# 20160428.net
KiCad netlist of a schematic drawn in Altium Designer
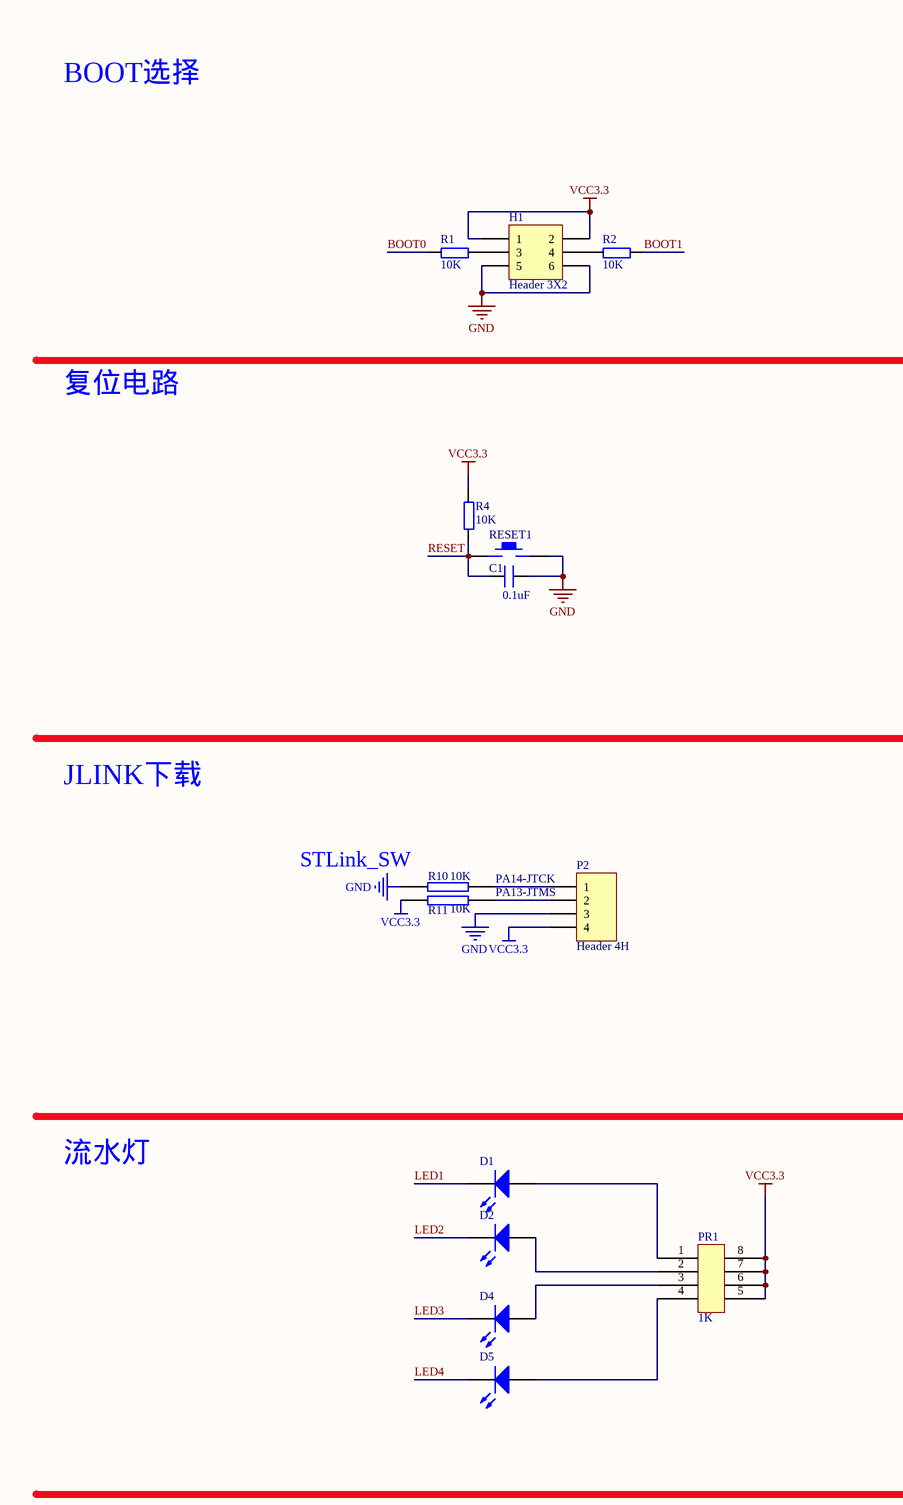
[diagram p0: 主控板20160428.SchDoc, top left]
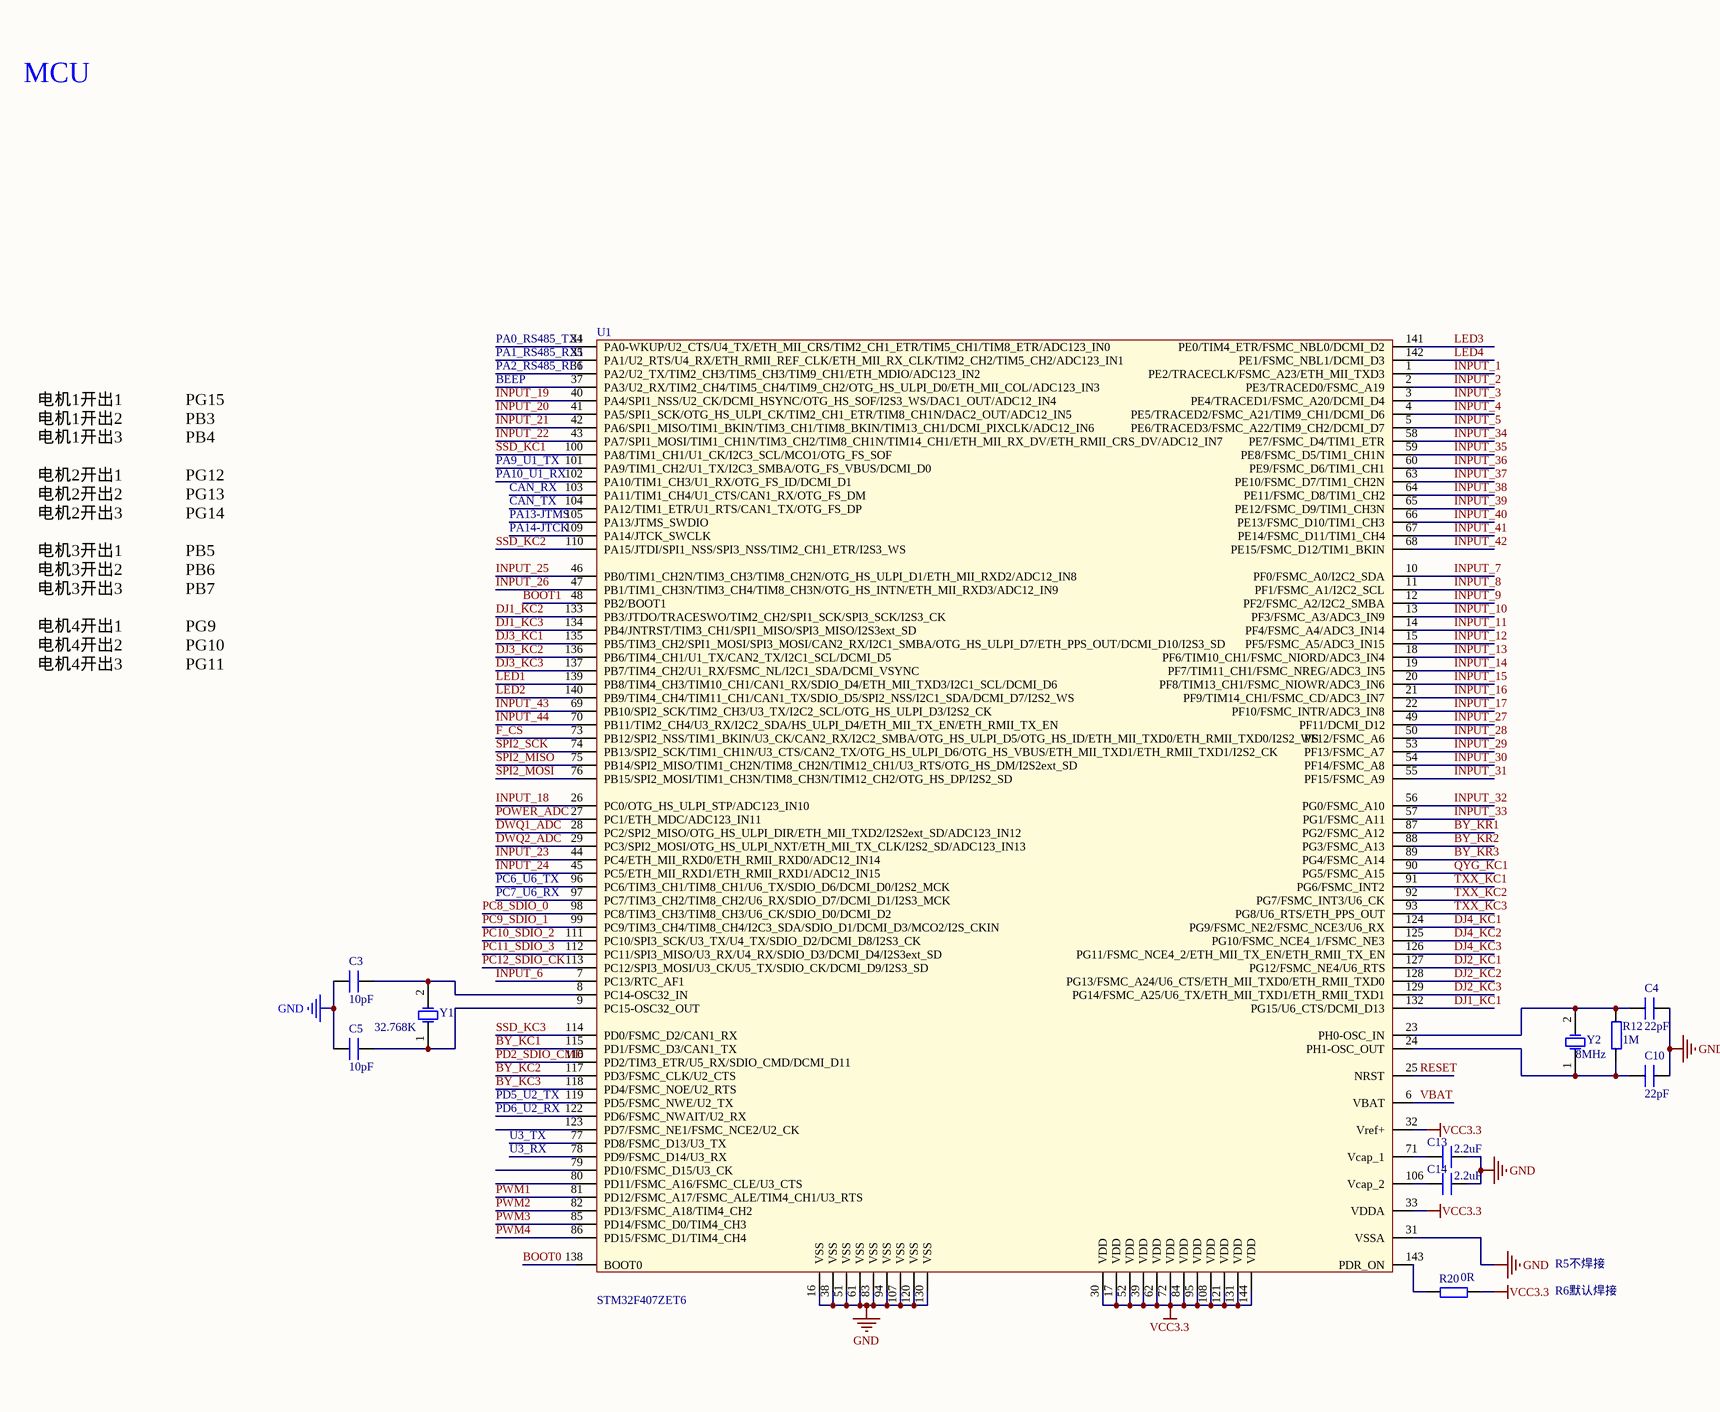
[diagram p1: 主控板20160428.SchDoc, top middle]
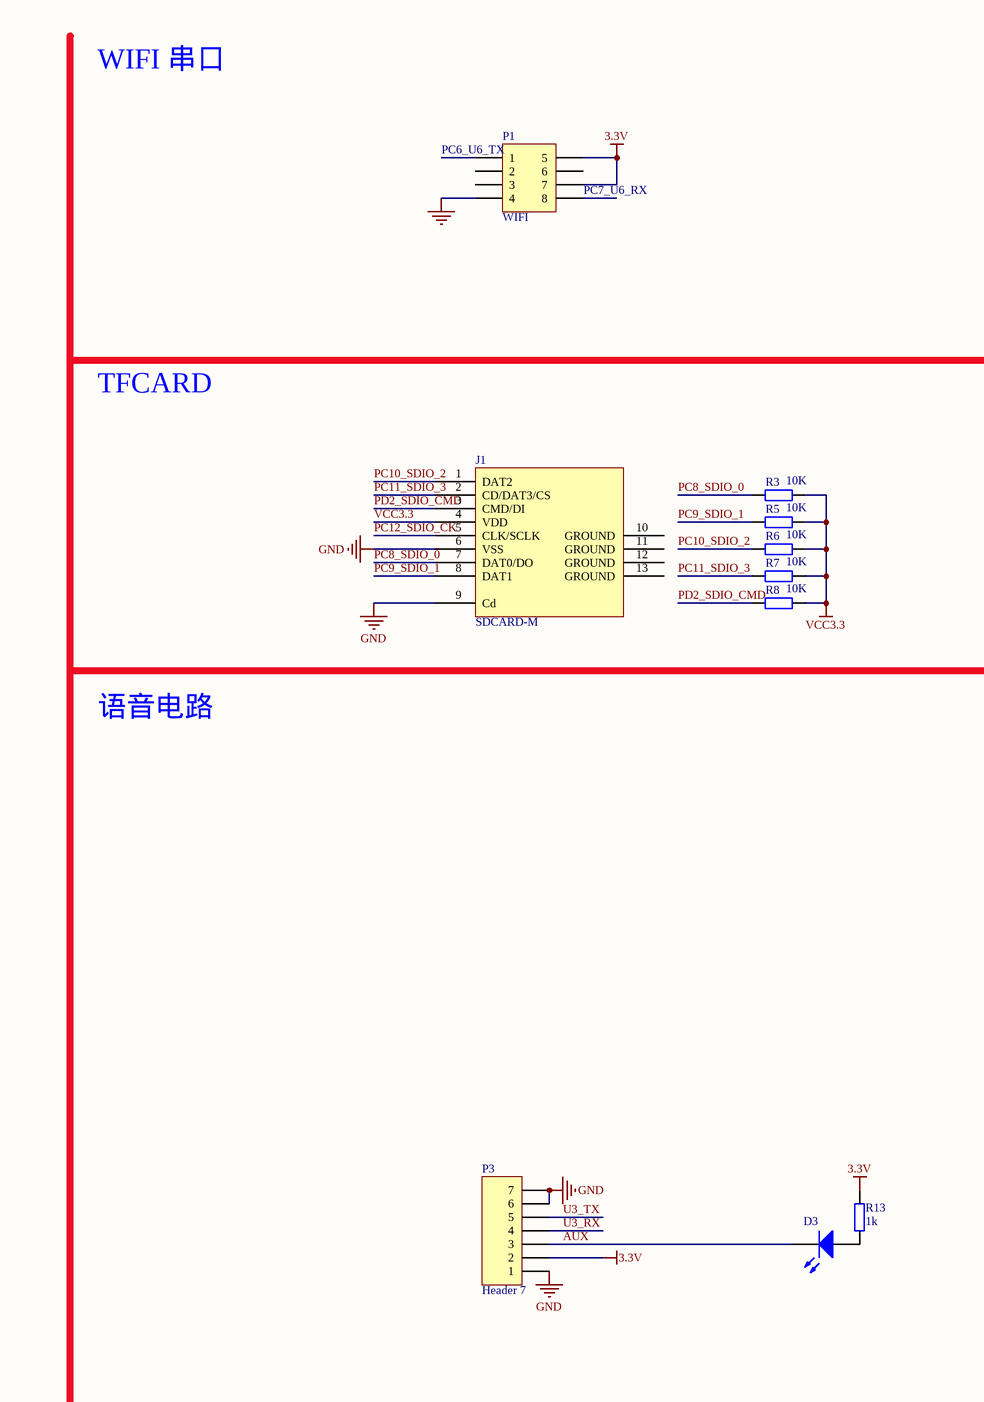
[diagram p2: 主控板20160428.SchDoc, top right]
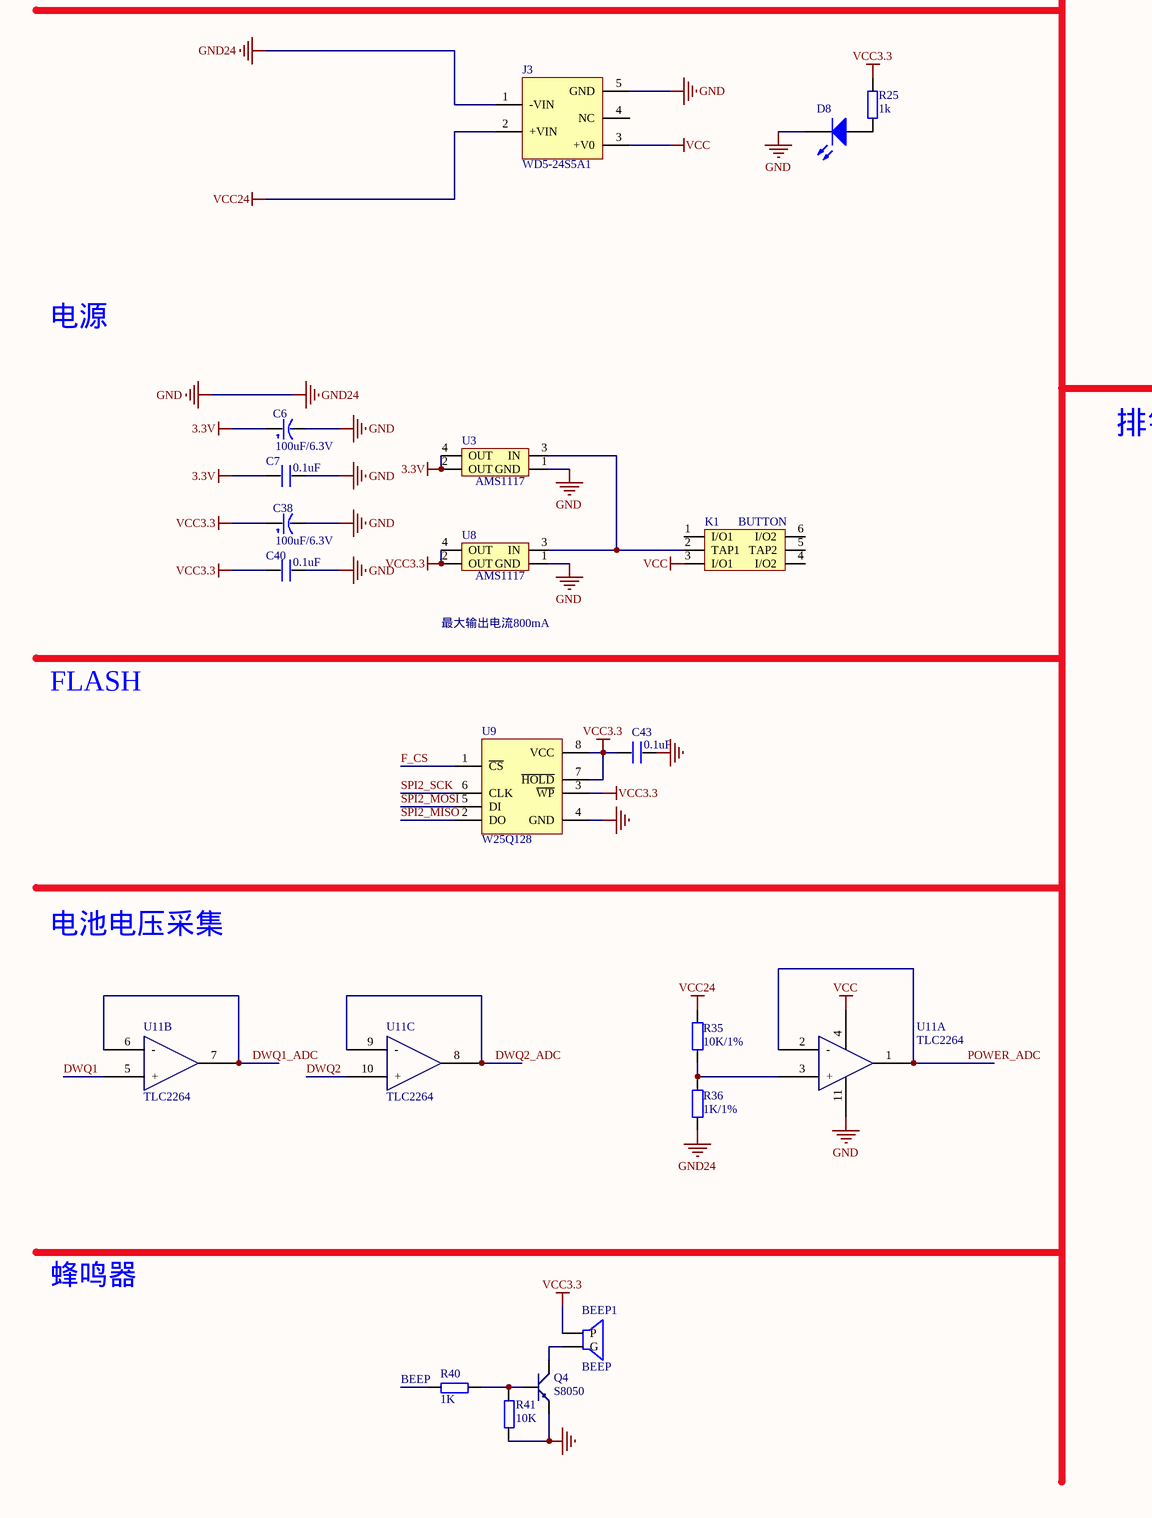
[diagram p3: 主控板20160428.SchDoc, bottom left]
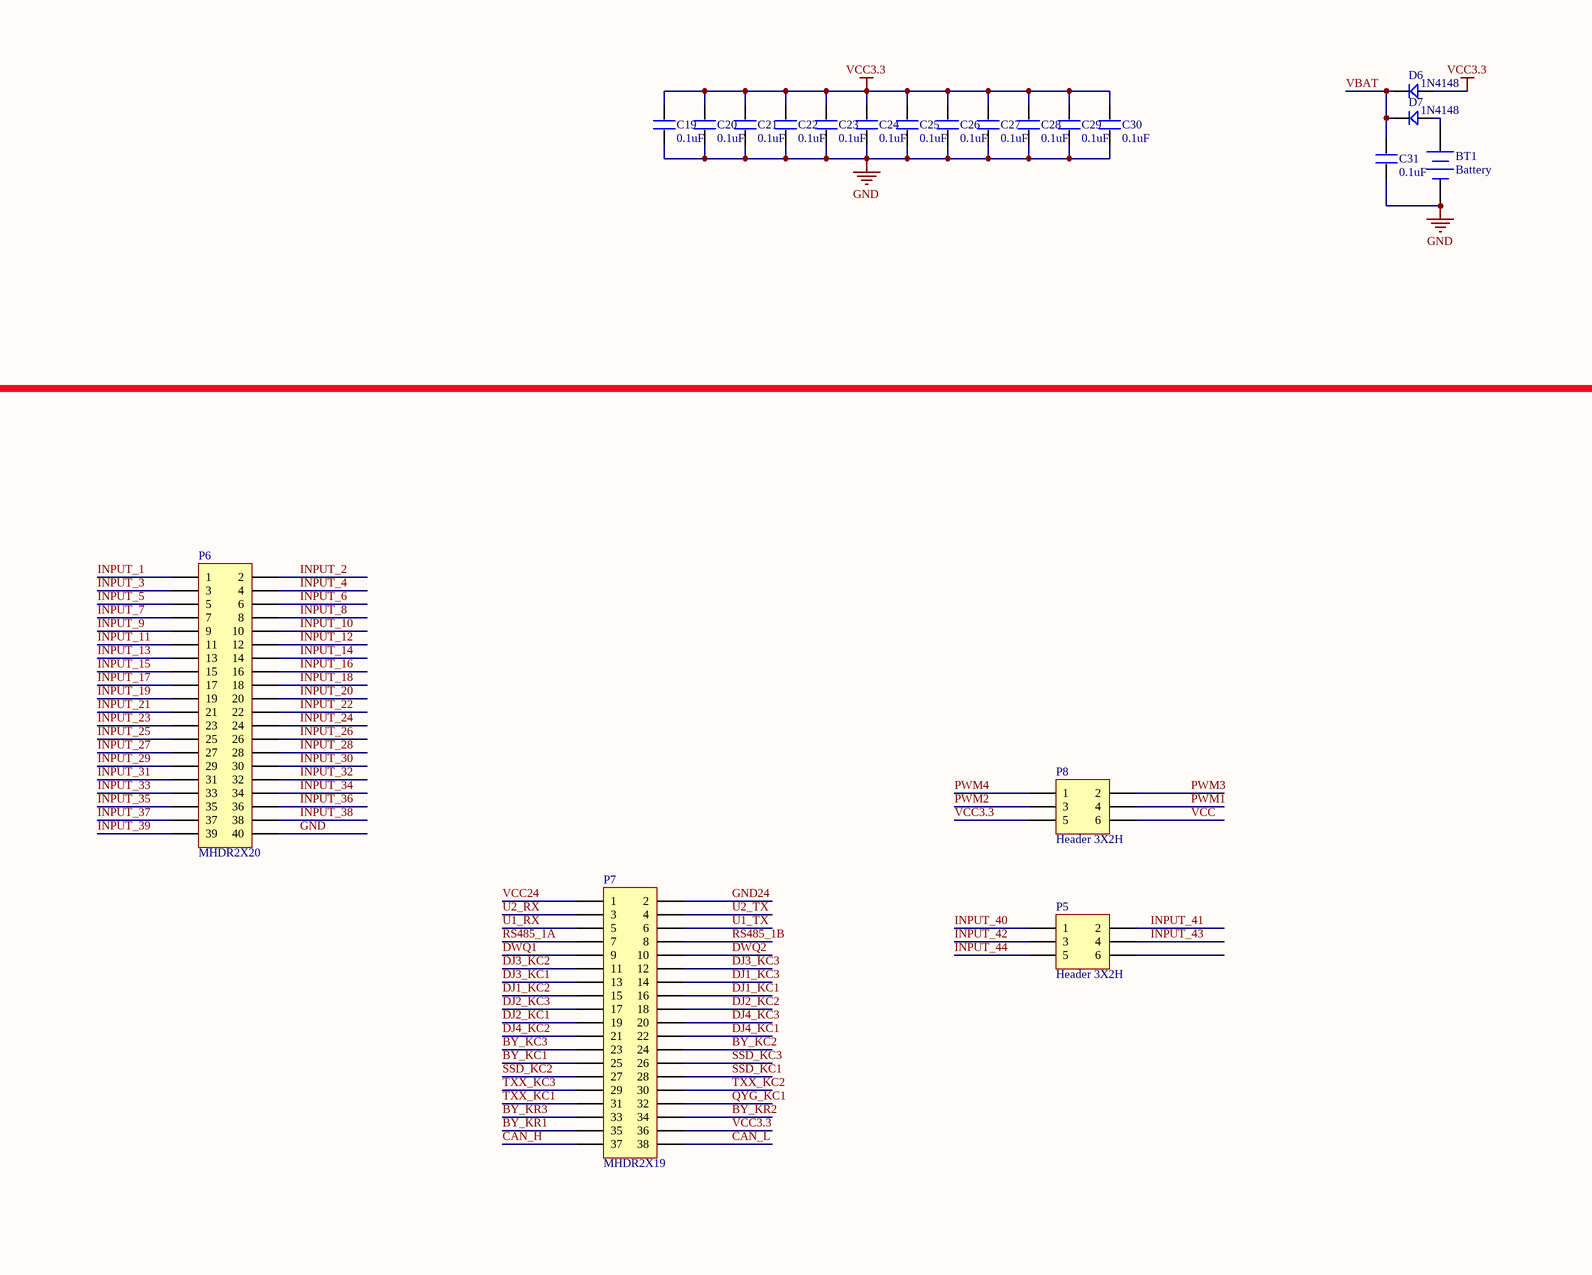
[diagram p4: 主控板20160428.SchDoc, bottom middle]
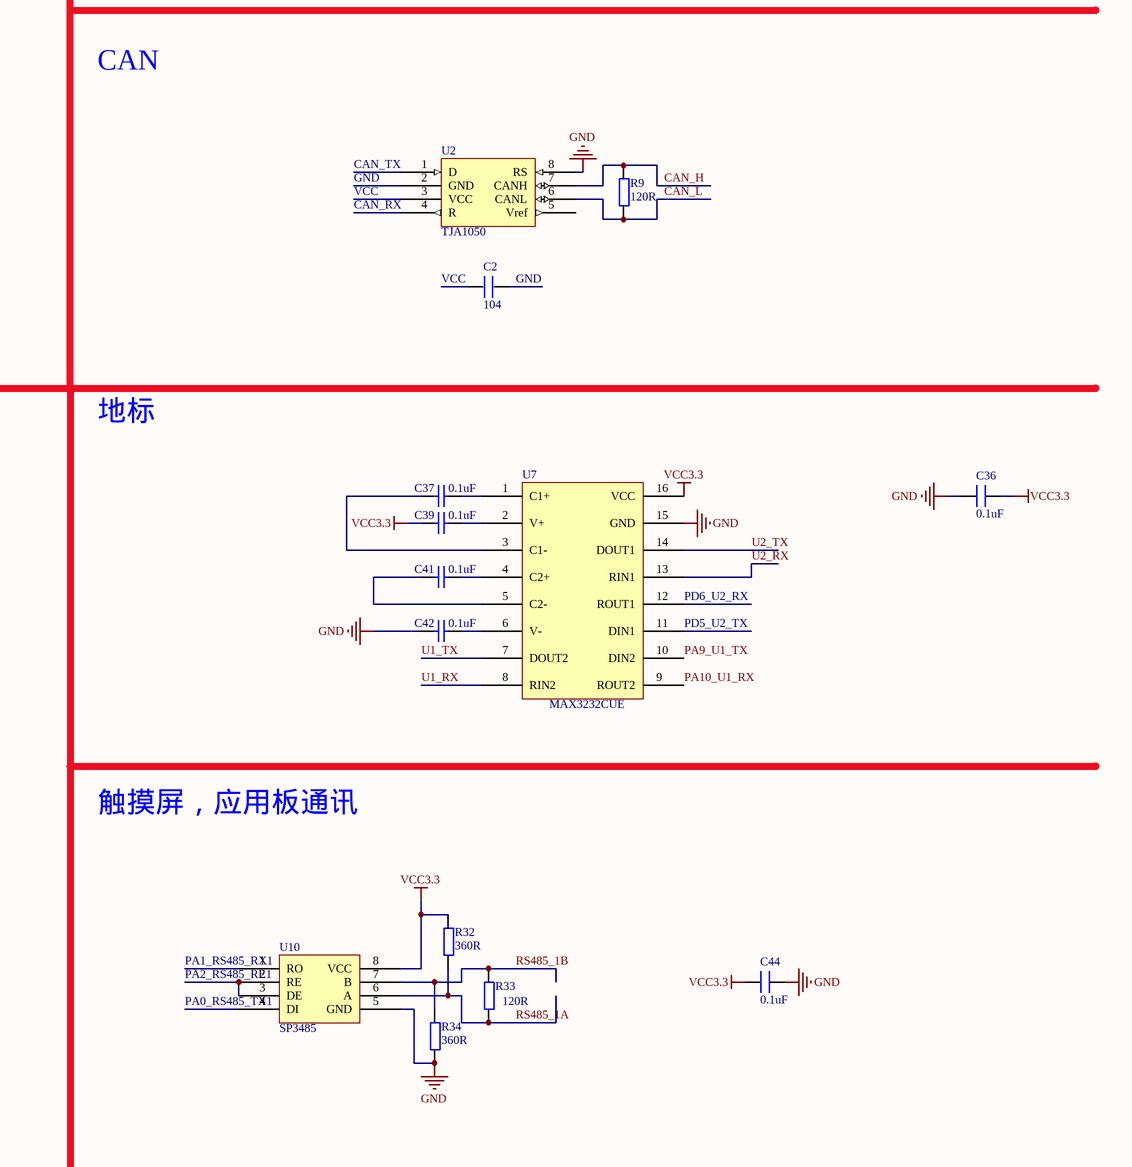
[diagram p5: 主控板20160428.SchDoc, bottom right]

(export (version "E")
  (design (tool "Eeschema 10.0.6"))
  (components
    (comp (ref "BEEP1") (value "BEEP") (footprint "BELL-5") (libsource (lib "WarShip V3_SCH") (part "BEEP")))
    (comp (ref "BT1")
      (value "Battery")
      (footprint "CR1220")
      (description "备份电池")
      (fields (field (name "PUBLISHER") "Altium Limited"))
      (libsource (lib "fszhang") (part "Battery"))
    )
    (comp (ref "C1") (value "0.1uF") (footprint "C0805") (libsource (lib "Explorer STM32F407封装库") (part "C")))
    (comp (ref "C2") (value "104") (footprint "C0805") (libsource (lib "Explorer STM32F407封装库") (part "C_3")))
    (comp (ref "C3")
      (value "10pF")
      (footprint "C0805")
      (libsource (lib "Explorer STM32F407封装库") (part "C_2"))
    )
    (comp (ref "C4")
      (value "22pF")
      (footprint "C0805")
      (libsource (lib "Explorer STM32F407封装库") (part "C_3"))
    )
    (comp (ref "C5")
      (value "10pF")
      (footprint "C0805")
      (libsource (lib "Explorer STM32F407封装库") (part "C_2"))
    )
    (comp (ref "C6") (value "100uF/6.3V") (footprint "3216") (libsource (lib "WarShip V3_SCH") (part "CAP")))
    (comp (ref "C7") (value "0.1uF") (footprint "C0805") (libsource (lib "WarShip V3_SCH") (part "C")))
    (comp (ref "C10")
      (value "22pF")
      (footprint "C0805")
      (libsource (lib "Explorer STM32F407封装库") (part "C_3"))
    )
    (comp (ref "C13")
      (value "2.2uF")
      (footprint "C0805")
      (libsource (lib "Explorer STM32F407封装库") (part "C"))
    )
    (comp (ref "C14")
      (value "2.2uF")
      (footprint "C0805")
      (libsource (lib "Explorer STM32F407封装库") (part "C"))
    )
    (comp (ref "C19") (value "0.1uF") (footprint "C0805") (libsource (lib "WarShip V3_SCH") (part "C")))
    (comp (ref "C20") (value "0.1uF") (footprint "C0805") (libsource (lib "WarShip V3_SCH") (part "C")))
    (comp (ref "C21") (value "0.1uF") (footprint "C0805") (libsource (lib "WarShip V3_SCH") (part "C")))
    (comp (ref "C22") (value "0.1uF") (footprint "C0805") (libsource (lib "WarShip V3_SCH") (part "C")))
    (comp (ref "C23") (value "0.1uF") (footprint "C0805") (libsource (lib "WarShip V3_SCH") (part "C")))
    (comp (ref "C24") (value "0.1uF") (footprint "C0805") (libsource (lib "WarShip V3_SCH") (part "C")))
    (comp (ref "C25") (value "0.1uF") (footprint "C0805") (libsource (lib "WarShip V3_SCH") (part "C")))
    (comp (ref "C26") (value "0.1uF") (footprint "C0805") (libsource (lib "WarShip V3_SCH") (part "C")))
    (comp (ref "C27") (value "0.1uF") (footprint "C0805") (libsource (lib "WarShip V3_SCH") (part "C")))
    (comp (ref "C28") (value "0.1uF") (footprint "C0805") (libsource (lib "WarShip V3_SCH") (part "C")))
    (comp (ref "C29") (value "0.1uF") (footprint "C0805") (libsource (lib "WarShip V3_SCH") (part "C")))
    (comp (ref "C30") (value "0.1uF") (footprint "C0805") (libsource (lib "WarShip V3_SCH") (part "C")))
    (comp (ref "C31")
      (value "0.1uF")
      (footprint "C0805")
      (libsource (lib "Explorer STM32F407封装库") (part "C_3"))
    )
    (comp (ref "C36")
      (value "0.1uF")
      (footprint "C0805")
      (libsource (lib "Explorer STM32F407封装库") (part "C_2"))
    )
    (comp (ref "C37")
      (value "0.1uF")
      (footprint "C0805")
      (description "Capacitor")
      (fields (field (name "PUBLISHER") "Altium Limited"))
      (libsource (lib "Miscellaneous Devices") (part "Cap"))
    )
    (comp (ref "C38") (value "100uF/6.3V") (footprint "3216") (libsource (lib "WarShip V3_SCH") (part "CAP")))
    (comp (ref "C39")
      (value "0.1uF")
      (footprint "C0805")
      (description "Capacitor")
      (fields (field (name "PUBLISHER") "Altium Limited"))
      (libsource (lib "Miscellaneous Devices") (part "Cap"))
    )
    (comp (ref "C40") (value "0.1uF") (footprint "C0805") (libsource (lib "WarShip V3_SCH") (part "C")))
    (comp (ref "C41")
      (value "0.1uF")
      (footprint "C0805")
      (description "Capacitor")
      (fields (field (name "PUBLISHER") "Altium Limited"))
      (libsource (lib "Miscellaneous Devices") (part "Cap"))
    )
    (comp (ref "C42")
      (value "0.1uF")
      (footprint "C0805")
      (description "Capacitor")
      (fields (field (name "PUBLISHER") "Altium Limited"))
      (libsource (lib "Miscellaneous Devices") (part "Cap"))
    )
    (comp (ref "C43") (value "0.1uF") (footprint "C0805") (libsource (lib "WarShip V3_SCH") (part "C")))
    (comp (ref "C44")
      (value "0.1uF")
      (footprint "C0805")
      (libsource (lib "Explorer STM32F407封装库") (part "C_3"))
    )
    (comp (ref "D1")
      (value "LED0")
      (footprint "LC-0805_LED_S1")
      (description "Typical INFRARED GaAs LED")
      (fields (field (name "PUBLISHER") "Altium Limited"))
      (libsource (lib "继电器板_1") (part "LED0"))
    )
    (comp (ref "D2")
      (value "LED0")
      (footprint "LC-0805_LED_S1")
      (description "Typical INFRARED GaAs LED")
      (fields (field (name "PUBLISHER") "Altium Limited"))
      (libsource (lib "继电器板_1") (part "LED0"))
    )
    (comp (ref "D3")
      (value "LED0")
      (footprint "LC-0805_LED_S1")
      (description "Typical INFRARED GaAs LED")
      (fields (field (name "PUBLISHER") "Altium Limited"))
      (libsource (lib "继电器板_1") (part "LED0"))
    )
    (comp (ref "D4")
      (value "LED0")
      (footprint "LC-0805_LED_S1")
      (description "Typical INFRARED GaAs LED")
      (fields (field (name "PUBLISHER") "Altium Limited"))
      (libsource (lib "继电器板_1") (part "LED0"))
    )
    (comp (ref "D5")
      (value "LED0")
      (footprint "LC-0805_LED_S1")
      (description "Typical INFRARED GaAs LED")
      (fields (field (name "PUBLISHER") "Altium Limited"))
      (libsource (lib "继电器板_1") (part "LED0"))
    )
    (comp (ref "D6")
      (value "1N4148")
      (footprint "DIDOE")
      (libsource (lib "Explorer STM32F407封装库") (part "D"))
    )
    (comp (ref "D7")
      (value "1N4148")
      (footprint "DIDOE")
      (libsource (lib "Explorer STM32F407封装库") (part "D"))
    )
    (comp (ref "D8")
      (value "LED0")
      (footprint "LC-0805_LED_S1")
      (description "Typical INFRARED GaAs LED")
      (fields (field (name "PUBLISHER") "Altium Limited"))
      (libsource (lib "继电器板_1") (part "LED0"))
    )
    (comp (ref "H1")
      (value "Header 3X2")
      (footprint "HDR2X3")
      (description "Header, 3-Pin, Dual row")
      (fields (field (name "PUBLISHER") "Altium Limited"))
      (libsource (lib "Explorer STM32F407封装库") (part "Header 3X2"))
    )
    (comp (ref "J1")
      (value "SDCARD-M")
      (footprint "SDCARD-M")
      (description "TF卡槽")
      (libsource (lib "fszhang") (part "SDCARD-M"))
    )
    (comp (ref "J3")
      (value "WD5-24S5A1")
      (footprint "WD5-24S3V3")
      (libsource (lib "*") (part "WD5-24S3V3A1"))
    )
    (comp (ref "K1")
      (value "BUTTON")
      (footprint "BTN8.5*8.5")
      (libsource (lib "WarShip V3_SCH") (part "BUTTON"))
    )
    (comp (ref "P1")
      (value "WIFI")
      (footprint "HDR2X4_CEN")
      (description "Header, 4-Pin, Dual row")
      (fields (field (name "PUBLISHER") "Altium Limited"))
      (libsource (lib "Miscellaneous Connectors") (part "Header 4X2A"))
    )
    (comp (ref "P2")
      (value "Header 4H")
      (footprint "IDE4")
      (description "Header, 4-Pin, Right Angle")
      (fields (field (name "PUBLISHER") "Altium Limited"))
      (libsource (lib "Miscellaneous Connectors") (part "Header 4H"))
    )
    (comp (ref "P3")
      (value "Header 7")
      (footprint "AS50-T27")
      (description "Header, 7-Pin")
      (fields (field (name "PUBLISHER") "Altium Limited"))
      (libsource (lib "Miscellaneous Connectors") (part "Header 7"))
    )
    (comp (ref "P5")
      (value "Header 3X2H")
      (footprint "HDR2X3")
      (description "Header, 3-Pin, Dual row, Right Angle")
      (fields (field (name "PUBLISHER") "Altium Limited"))
      (libsource (lib "Miscellaneous Connectors") (part "Header 3X2H"))
    )
    (comp (ref "P6")
      (value "MHDR2X20")
      (footprint "DIP-2X20")
      (description "Header, 20-Pin, Dual row")
      (fields (field (name "PUBLISHER") "Altium Limited"))
      (libsource (lib "Miscellaneous Connectors") (part "MHDR2X20"))
    )
    (comp (ref "P7")
      (value "MHDR2X19")
      (footprint "DIP-2X19")
      (description "Header, 19-Pin, Dual row")
      (fields (field (name "PUBLISHER") "Altium Limited"))
      (libsource (lib "Miscellaneous Connectors") (part "MHDR2X19"))
    )
    (comp (ref "P8")
      (value "Header 3X2H")
      (footprint "HDR2X3")
      (description "Header, 3-Pin, Dual row, Right Angle")
      (fields (field (name "PUBLISHER") "Altium Limited"))
      (libsource (lib "Miscellaneous Connectors") (part "Header 3X2H"))
    )
    (comp (ref "PR1") (value "1K") (footprint "TPPZ") (libsource (lib "EXPLORER") (part "PZ")))
    (comp (ref "Q4")
      (value "S8050")
      (footprint "SOT-23R")
      (description "8050/BCW846/BCW847")
      (libsource (lib "WarShip V3_SCH") (part "NPN"))
    )
    (comp (ref "R1") (value "10K") (footprint "0805") (libsource (lib "Explorer STM32F407封装库") (part "R_1")))
    (comp (ref "R2") (value "10K") (footprint "0805") (libsource (lib "Explorer STM32F407封装库") (part "R_1")))
    (comp (ref "R3")
      (value "10K")
      (footprint "0805")
      (description "贴片电阻")
      (fields (field (name "PUBLISHER") "Altium Limited"))
      (libsource (lib "fszhang") (part "Res1"))
    )
    (comp (ref "R4") (value "10K") (footprint "0805") (libsource (lib "Explorer STM32F407封装库") (part "R_2")))
    (comp (ref "R5")
      (value "10K")
      (footprint "0805")
      (description "贴片电阻")
      (fields (field (name "PUBLISHER") "Altium Limited"))
      (libsource (lib "fszhang") (part "Res1"))
    )
    (comp (ref "R6")
      (value "10K")
      (footprint "0805")
      (description "贴片电阻")
      (fields (field (name "PUBLISHER") "Altium Limited"))
      (libsource (lib "fszhang") (part "Res1"))
    )
    (comp (ref "R7")
      (value "10K")
      (footprint "0805")
      (description "贴片电阻")
      (fields (field (name "PUBLISHER") "Altium Limited"))
      (libsource (lib "fszhang") (part "Res1"))
    )
    (comp (ref "R8")
      (value "10K")
      (footprint "0805")
      (description "贴片电阻")
      (fields (field (name "PUBLISHER") "Altium Limited"))
      (libsource (lib "fszhang") (part "Res1"))
    )
    (comp (ref "R9") (value "120R") (footprint "0805") (libsource (lib "Explorer STM32F407封装库") (part "R_2")))
    (comp (ref "R10") (value "10K") (footprint "0805") (libsource (lib "*") (part "RES2")))
    (comp (ref "R11") (value "10K") (footprint "0805") (libsource (lib "*") (part "RES2")))
    (comp (ref "R12") (value "1M") (footprint "0805") (libsource (lib "Explorer STM32F407封装库") (part "R")))
    (comp (ref "R13") (value "1k") (footprint "0805") (libsource (lib "Explorer STM32F407封装库") (part "R_2")))
    (comp (ref "R20") (value "0R") (footprint "0805") (libsource (lib "Explorer STM32F407封装库") (part "R_2")))
    (comp (ref "R25") (value "1k") (footprint "0805") (libsource (lib "Explorer STM32F407封装库") (part "R_2")))
    (comp (ref "R32")
      (value "360R")
      (footprint "0805")
      (libsource (lib "Explorer STM32F407封装库") (part "R_2"))
    )
    (comp (ref "R33")
      (value "120R")
      (footprint "0805")
      (libsource (lib "Explorer STM32F407封装库") (part "R_2"))
    )
    (comp (ref "R34")
      (value "360R")
      (footprint "0805")
      (libsource (lib "Explorer STM32F407封装库") (part "R_2"))
    )
    (comp (ref "R35")
      (value "10K/1%")
      (footprint "0805")
      (description "Resistor")
      (fields (field (name "PUBLISHER") "Altium Limited"))
      (libsource (lib "Miscellaneous Devices") (part "Res2"))
    )
    (comp (ref "R36")
      (value "1K/1%")
      (footprint "0805")
      (description "Resistor")
      (fields (field (name "PUBLISHER") "Altium Limited"))
      (libsource (lib "Miscellaneous Devices") (part "Res2"))
    )
    (comp (ref "R40") (value "1K") (footprint "0805") (libsource (lib "WarShip V3_SCH") (part "R")))
    (comp (ref "R41") (value "10K") (footprint "0805") (libsource (lib "WarShip V3_SCH") (part "R")))
    (comp (ref "RESET1")
      (value "KEY_M")
      (footprint "SW_PB2_A1")
      (libsource (lib "Explorer STM32F407封装库") (part "KEY_M"))
    )
    (comp (ref "U1")
      (value "STM32F407ZET6")
      (footprint "LQFP144")
      (libsource (lib "Explorer STM32F407封装库") (part "STM32F407ZET6"))
    )
    (comp (ref "U2")
      (value "TJA1050")
      (footprint "SOP-8")
      (libsource (lib "Explorer STM32F407封装库") (part "SN65HVD230D"))
    )
    (comp (ref "U3")
      (value "AMS1117")
      (footprint "SOT-223")
      (libsource (lib "WarShip V3_SCH") (part "AMS1117"))
    )
    (comp (ref "U7")
      (value "MAX3232CUE")
      (footprint "SO-16")
      (libsource (lib "Smart_board_v1") (part "MAX3232CUE"))
    )
    (comp (ref "U8")
      (value "AMS1117")
      (footprint "SOT-223")
      (libsource (lib "WarShip V3_SCH") (part "AMS1117"))
    )
    (comp (ref "U9")
      (value "W25Q128")
      (footprint "SOIC8_W")
      (description "SPI FLASH")
      (libsource (lib "fszhang") (part "W25QXX"))
    )
    (comp (ref "U10") (value "SP3485") (footprint "SO-8") (libsource (lib "Schlib1") (part "SP3485")))
    (comp (ref "U11") (value "TLC2264") (footprint "SO-14") (libsource (lib "EXPLORER") (part "TLC2264")))
    (comp (ref "Y1")
      (value "32.768K")
      (footprint "XTAL-32768")
      (description "Crystal Oscillator")
      (fields (field (name "PUBLISHER") "Altium Limited"))
      (libsource (lib "Explorer STM32F407封装库") (part "XTAL_1"))
    )
    (comp (ref "Y2")
      (value "8MHz")
      (footprint "XTAL_US")
      (description "Crystal Oscillator")
      (fields (field (name "PUBLISHER") "Altium Limited"))
      (libsource (lib "Explorer STM32F407封装库") (part "XTAL"))
    )
  )
  (nets
    (net (code "1") (name "/AUX") (class "Default")
      (node (ref "D3") (pin "K") (pinfunction "K_K") (pintype "passive"))
      (node (ref "P3") (pin "3") (pinfunction "3_3") (pintype "passive"))
    )
    (net (code "2") (name "/BEEP") (class "Default")
      (node (ref "R40") (pin "1") (pintype "passive"))
      (node (ref "U1") (pin "37") (pinfunction "PA3/U2_RX/TIM2_CH4/TIM5_CH4/TIM9_CH2/OTG_HS_ULPI_D0/ETH_MII_COL/ADC123_IN3_37") (pintype "passive"))
    )
    (net (code "3") (name "/BOOT0") (class "Default")
      (node (ref "R1") (pin "1") (pintype "passive"))
      (node (ref "U1") (pin "138") (pinfunction "BOOT0_138") (pintype "passive"))
    )
    (net (code "4") (name "/BOOT1") (class "Default")
      (node (ref "R2") (pin "2") (pintype "passive"))
      (node (ref "U1") (pin "48") (pinfunction "PB2/BOOT1_48") (pintype "passive"))
    )
    (net (code "5") (name "/BY_KC1") (class "Default")
      (node (ref "P7") (pin "25") (pinfunction "25_25") (pintype "passive"))
      (node (ref "U1") (pin "115") (pinfunction "PD1/FSMC_D3/CAN1_TX_115") (pintype "passive"))
    )
    (net (code "6") (name "/BY_KC2") (class "Default")
      (node (ref "P7") (pin "24") (pinfunction "24_24") (pintype "passive"))
      (node (ref "U1") (pin "117") (pinfunction "PD3/FSMC_CLK/U2_CTS_117") (pintype "passive"))
    )
    (net (code "7") (name "/BY_KC3") (class "Default")
      (node (ref "P7") (pin "23") (pinfunction "23_23") (pintype "passive"))
      (node (ref "U1") (pin "118") (pinfunction "PD4/FSMC_NOE/U2_RTS_118") (pintype "passive"))
    )
    (net (code "8") (name "/BY_KR1") (class "Default")
      (node (ref "P7") (pin "35") (pinfunction "35_35") (pintype "passive"))
      (node (ref "U1") (pin "87") (pinfunction "PG2/FSMC_A12_87") (pintype "passive"))
    )
    (net (code "9") (name "/BY_KR2") (class "Default")
      (node (ref "P7") (pin "34") (pinfunction "34_34") (pintype "passive"))
      (node (ref "U1") (pin "88") (pinfunction "PG3/FSMC_A13_88") (pintype "passive"))
    )
    (net (code "10") (name "/BY_KR3") (class "Default")
      (node (ref "P7") (pin "33") (pinfunction "33_33") (pintype "passive"))
      (node (ref "U1") (pin "89") (pinfunction "PG4/FSMC_A14_89") (pintype "passive"))
    )
    (net (code "11") (name "/CAN_H") (class "Default")
      (node (ref "P7") (pin "37") (pinfunction "37_37") (pintype "passive"))
      (node (ref "R9") (pin "2") (pintype "passive"))
      (node (ref "U2") (pin "7") (pinfunction "CANH_7") (pintype "bidirectional"))
    )
    (net (code "12") (name "/CAN_L") (class "Default")
      (node (ref "P7") (pin "38") (pinfunction "38_38") (pintype "passive"))
      (node (ref "R9") (pin "1") (pintype "passive"))
      (node (ref "U2") (pin "6") (pinfunction "CANL_6") (pintype "bidirectional"))
    )
    (net (code "13") (name "/CAN_RX") (class "Default")
      (node (ref "U1") (pin "103") (pinfunction "PA11/TIM1_CH4/U1_CTS/CAN1_RX/OTG_FS_DM_103") (pintype "passive"))
      (node (ref "U2") (pin "4") (pinfunction "R_4") (pintype "output"))
    )
    (net (code "14") (name "/CAN_TX") (class "Default")
      (node (ref "U1") (pin "104") (pinfunction "PA12/TIM1_ETR/U1_RTS/CAN1_TX/OTG_FS_DP_104") (pintype "passive"))
      (node (ref "U2") (pin "1") (pinfunction "D_1") (pintype "input"))
    )
    (net (code "15") (name "/DJ1_KC1") (class "Default")
      (node (ref "P7") (pin "16") (pinfunction "16_16") (pintype "passive"))
      (node (ref "U1") (pin "132") (pinfunction "PG15/U6_CTS/DCMI_D13_132") (pintype "passive"))
    )
    (net (code "16") (name "/DJ1_KC2") (class "Default")
      (node (ref "P7") (pin "15") (pinfunction "15_15") (pintype "passive"))
      (node (ref "U1") (pin "133") (pinfunction "PB3/JTDO/TRACESWO/TIM2_CH2/SPI1_SCK/SPI3_SCK/I2S3_CK_133") (pintype "passive"))
    )
    (net (code "17") (name "/DJ1_KC3") (class "Default")
      (node (ref "P7") (pin "14") (pinfunction "14_14") (pintype "passive"))
      (node (ref "U1") (pin "134") (pinfunction "PB4/JNTRST/TIM3_CH1/SPI1_MISO/SPI3_MISO/I2S3ext_SD_134") (pintype "passive"))
    )
    (net (code "18") (name "/DJ2_KC1") (class "Default")
      (node (ref "P7") (pin "19") (pinfunction "19_19") (pintype "passive"))
      (node (ref "U1") (pin "127") (pinfunction "PG12/FSMC_NE4/U6_RTS_127") (pintype "passive"))
    )
    (net (code "19") (name "/DJ2_KC2") (class "Default")
      (node (ref "P7") (pin "18") (pinfunction "18_18") (pintype "passive"))
      (node (ref "U1") (pin "128") (pinfunction "PG13/FSMC_A24/U6_CTS/ETH_MII_TXD0/ETH_RMII_TXD0_128") (pintype "passive"))
    )
    (net (code "20") (name "/DJ2_KC3") (class "Default")
      (node (ref "P7") (pin "17") (pinfunction "17_17") (pintype "passive"))
      (node (ref "U1") (pin "129") (pinfunction "PG14/FSMC_A25/U6_TX/ETH_MII_TXD1/ETH_RMII_TXD1_129") (pintype "passive"))
    )
    (net (code "21") (name "/DJ3_KC1") (class "Default")
      (node (ref "P7") (pin "13") (pinfunction "13_13") (pintype "passive"))
      (node (ref "U1") (pin "135") (pinfunction "PB5/TIM3_CH2/SPI1_MOSI/SPI3_MOSI/CAN2_RX/I2C1_SMBA/OTG_HS_ULPI_D7/ETH_PPS_OUT/DCMI_D10/I2S3_SD_135") (pintype "passive"))
    )
    (net (code "22") (name "/DJ3_KC2") (class "Default")
      (node (ref "P7") (pin "11") (pinfunction "11_11") (pintype "passive"))
      (node (ref "U1") (pin "136") (pinfunction "PB6/TIM4_CH1/U1_TX/CAN2_TX/I2C1_SCL/DCMI_D5_136") (pintype "passive"))
    )
    (net (code "23") (name "/DJ3_KC3") (class "Default")
      (node (ref "P7") (pin "12") (pinfunction "12_12") (pintype "passive"))
      (node (ref "U1") (pin "137") (pinfunction "PB7/TIM4_CH2/U1_RX/FSMC_NL/I2C1_SDA/DCMI_VSYNC_137") (pintype "passive"))
    )
    (net (code "24") (name "/DJ4_KC1") (class "Default")
      (node (ref "P7") (pin "22") (pinfunction "22_22") (pintype "passive"))
      (node (ref "U1") (pin "124") (pinfunction "PG9/FSMC_NE2/FSMC_NCE3/U6_RX_124") (pintype "passive"))
    )
    (net (code "25") (name "/DJ4_KC2") (class "Default")
      (node (ref "P7") (pin "21") (pinfunction "21_21") (pintype "passive"))
      (node (ref "U1") (pin "125") (pinfunction "PG10/FSMC_NCE4_1/FSMC_NE3_125") (pintype "passive"))
    )
    (net (code "26") (name "/DJ4_KC3") (class "Default")
      (node (ref "P7") (pin "20") (pinfunction "20_20") (pintype "passive"))
      (node (ref "U1") (pin "126") (pinfunction "PG11/FSMC_NCE4_2/ETH_MII_TX_EN/ETH_RMII_TX_EN_126") (pintype "passive"))
    )
    (net (code "27") (name "/DWQ1") (class "Default")
      (node (ref "P7") (pin "9") (pinfunction "9_9") (pintype "passive"))
      (node (ref "U11") (pin "5") (pinfunction "+_5") (pintype "passive"))
    )
    (net (code "28") (name "/DWQ1_ADC") (class "Default")
      (node (ref "U1") (pin "28") (pinfunction "PC2/SPI2_MISO/OTG_HS_ULPI_DIR/ETH_MII_TXD2/I2S2ext_SD/ADC123_IN12_28") (pintype "passive"))
      (node (ref "U11") (pin "6") (pinfunction "-_6") (pintype "passive"))
      (node (ref "U11") (pin "7") (pinfunction "2OUT_7") (pintype "passive"))
    )
    (net (code "29") (name "/DWQ2") (class "Default")
      (node (ref "P7") (pin "10") (pinfunction "10_10") (pintype "passive"))
      (node (ref "U11") (pin "10") (pinfunction "+_10") (pintype "passive"))
    )
    (net (code "30") (name "/DWQ2_ADC") (class "Default")
      (node (ref "U1") (pin "29") (pinfunction "PC3/SPI2_MOSI/OTG_HS_ULPI_NXT/ETH_MII_TX_CLK/I2S2_SD/ADC123_IN13_29") (pintype "passive"))
      (node (ref "U11") (pin "8") (pinfunction "3OUT_8") (pintype "passive"))
      (node (ref "U11") (pin "9") (pinfunction "-_9") (pintype "passive"))
    )
    (net (code "31") (name "/F_CS") (class "Default")
      (node (ref "U1") (pin "73") (pinfunction "PB12/SPI2_NSS/TIM1_BKIN/U3_CK/CAN2_RX/I2C2_SMBA/OTG_HS_ULPI_D5/OTG_HS_ID/ETH_MII_TXD0/ETH_RMII_TXD0/I2S2_WS_73") (pintype "passive"))
      (node (ref "U9") (pin "1") (pinfunction "~{CS}_1") (pintype "passive"))
    )
    (net (code "32") (name "/INPUT_1") (class "Default")
      (node (ref "P6") (pin "1") (pinfunction "1_1") (pintype "passive"))
      (node (ref "U1") (pin "1") (pinfunction "PE2/TRACECLK/FSMC_A23/ETH_MII_TXD3_1") (pintype "passive"))
    )
    (net (code "33") (name "/INPUT_2") (class "Default")
      (node (ref "P6") (pin "2") (pinfunction "2_2") (pintype "passive"))
      (node (ref "U1") (pin "2") (pinfunction "PE3/TRACED0/FSMC_A19_2") (pintype "passive"))
    )
    (net (code "34") (name "/INPUT_3") (class "Default")
      (node (ref "P6") (pin "3") (pinfunction "3_3") (pintype "passive"))
      (node (ref "U1") (pin "3") (pinfunction "PE4/TRACED1/FSMC_A20/DCMI_D4_3") (pintype "passive"))
    )
    (net (code "35") (name "/INPUT_4") (class "Default")
      (node (ref "P6") (pin "4") (pinfunction "4_4") (pintype "passive"))
      (node (ref "U1") (pin "4") (pinfunction "PE5/TRACED2/FSMC_A21/TIM9_CH1/DCMI_D6_4") (pintype "passive"))
    )
    (net (code "36") (name "/INPUT_5") (class "Default")
      (node (ref "P6") (pin "5") (pinfunction "5_5") (pintype "passive"))
      (node (ref "U1") (pin "5") (pinfunction "PE6/TRACED3/FSMC_A22/TIM9_CH2/DCMI_D7_5") (pintype "passive"))
    )
    (net (code "37") (name "/INPUT_6") (class "Default")
      (node (ref "P6") (pin "6") (pinfunction "6_6") (pintype "passive"))
      (node (ref "U1") (pin "7") (pinfunction "PC13/RTC_AF1_7") (pintype "passive"))
    )
    (net (code "38") (name "/INPUT_7") (class "Default")
      (node (ref "P6") (pin "7") (pinfunction "7_7") (pintype "passive"))
      (node (ref "U1") (pin "10") (pinfunction "PF0/FSMC_A0/I2C2_SDA_10") (pintype "passive"))
    )
    (net (code "39") (name "/INPUT_8") (class "Default")
      (node (ref "P6") (pin "8") (pinfunction "8_8") (pintype "passive"))
      (node (ref "U1") (pin "11") (pinfunction "PF1/FSMC_A1/I2C2_SCL_11") (pintype "passive"))
    )
    (net (code "40") (name "/INPUT_9") (class "Default")
      (node (ref "P6") (pin "9") (pinfunction "9_9") (pintype "passive"))
      (node (ref "U1") (pin "12") (pinfunction "PF2/FSMC_A2/I2C2_SMBA_12") (pintype "passive"))
    )
    (net (code "41") (name "/INPUT_10") (class "Default")
      (node (ref "P6") (pin "10") (pinfunction "10_10") (pintype "passive"))
      (node (ref "U1") (pin "13") (pinfunction "PF3/FSMC_A3/ADC3_IN9_13") (pintype "passive"))
    )
    (net (code "42") (name "/INPUT_11") (class "Default")
      (node (ref "P6") (pin "11") (pinfunction "11_11") (pintype "passive"))
      (node (ref "U1") (pin "14") (pinfunction "PF4/FSMC_A4/ADC3_IN14_14") (pintype "passive"))
    )
    (net (code "43") (name "/INPUT_12") (class "Default")
      (node (ref "P6") (pin "12") (pinfunction "12_12") (pintype "passive"))
      (node (ref "U1") (pin "15") (pinfunction "PF5/FSMC_A5/ADC3_IN15_15") (pintype "passive"))
    )
    (net (code "44") (name "/INPUT_13") (class "Default")
      (node (ref "P6") (pin "13") (pinfunction "13_13") (pintype "passive"))
      (node (ref "U1") (pin "18") (pinfunction "PF6/TIM10_CH1/FSMC_NIORD/ADC3_IN4_18") (pintype "passive"))
    )
    (net (code "45") (name "/INPUT_14") (class "Default")
      (node (ref "P6") (pin "14") (pinfunction "14_14") (pintype "passive"))
      (node (ref "U1") (pin "19") (pinfunction "PF7/TIM11_CH1/FSMC_NREG/ADC3_IN5_19") (pintype "passive"))
    )
    (net (code "46") (name "/INPUT_15") (class "Default")
      (node (ref "P6") (pin "15") (pinfunction "15_15") (pintype "passive"))
      (node (ref "U1") (pin "20") (pinfunction "PF8/TIM13_CH1/FSMC_NIOWR/ADC3_IN6_20") (pintype "passive"))
    )
    (net (code "47") (name "/INPUT_16") (class "Default")
      (node (ref "P6") (pin "16") (pinfunction "16_16") (pintype "passive"))
      (node (ref "U1") (pin "21") (pinfunction "PF9/TIM14_CH1/FSMC_CD/ADC3_IN7_21") (pintype "passive"))
    )
    (net (code "48") (name "/INPUT_17") (class "Default")
      (node (ref "P6") (pin "17") (pinfunction "17_17") (pintype "passive"))
      (node (ref "U1") (pin "22") (pinfunction "PF10/FSMC_INTR/ADC3_IN8_22") (pintype "passive"))
    )
    (net (code "49") (name "/INPUT_18") (class "Default")
      (node (ref "P6") (pin "18") (pinfunction "18_18") (pintype "passive"))
      (node (ref "U1") (pin "26") (pinfunction "PC0/OTG_HS_ULPI_STP/ADC123_IN10_26") (pintype "passive"))
    )
    (net (code "50") (name "/INPUT_19") (class "Default")
      (node (ref "P6") (pin "19") (pinfunction "19_19") (pintype "passive"))
      (node (ref "U1") (pin "40") (pinfunction "PA4/SPI1_NSS/U2_CK/DCMI_HSYNC/OTG_HS_SOF/I2S3_WS/DAC1_OUT/ADC12_IN4_40") (pintype "passive"))
    )
    (net (code "51") (name "/INPUT_20") (class "Default")
      (node (ref "P6") (pin "20") (pinfunction "20_20") (pintype "passive"))
      (node (ref "U1") (pin "41") (pinfunction "PA5/SPI1_SCK/OTG_HS_ULPI_CK/TIM2_CH1_ETR/TIM8_CH1N/DAC2_OUT/ADC12_IN5_41") (pintype "passive"))
    )
    (net (code "52") (name "/INPUT_21") (class "Default")
      (node (ref "P6") (pin "21") (pinfunction "21_21") (pintype "passive"))
      (node (ref "U1") (pin "42") (pinfunction "PA6/SPI1_MISO/TIM1_BKIN/TIM3_CH1/TIM8_BKIN/TIM13_CH1/DCMI_PIXCLK/ADC12_IN6_42") (pintype "passive"))
    )
    (net (code "53") (name "/INPUT_22") (class "Default")
      (node (ref "P6") (pin "22") (pinfunction "22_22") (pintype "passive"))
      (node (ref "U1") (pin "43") (pinfunction "PA7/SPI1_MOSI/TIM1_CH1N/TIM3_CH2/TIM8_CH1N/TIM14_CH1/ETH_MII_RX_DV/ETH_RMII_CRS_DV/ADC12_IN7_43") (pintype "passive"))
    )
    (net (code "54") (name "/INPUT_23") (class "Default")
      (node (ref "P6") (pin "23") (pinfunction "23_23") (pintype "passive"))
      (node (ref "U1") (pin "44") (pinfunction "PC4/ETH_MII_RXD0/ETH_RMII_RXD0/ADC12_IN14_44") (pintype "passive"))
    )
    (net (code "55") (name "/INPUT_24") (class "Default")
      (node (ref "P6") (pin "24") (pinfunction "24_24") (pintype "passive"))
      (node (ref "U1") (pin "45") (pinfunction "PC5/ETH_MII_RXD1/ETH_RMII_RXD1/ADC12_IN15_45") (pintype "passive"))
    )
    (net (code "56") (name "/INPUT_25") (class "Default")
      (node (ref "P6") (pin "25") (pinfunction "25_25") (pintype "passive"))
      (node (ref "U1") (pin "46") (pinfunction "PB0/TIM1_CH2N/TIM3_CH3/TIM8_CH2N/OTG_HS_ULPI_D1/ETH_MII_RXD2/ADC12_IN8_46") (pintype "passive"))
    )
    (net (code "57") (name "/INPUT_26") (class "Default")
      (node (ref "P6") (pin "26") (pinfunction "26_26") (pintype "passive"))
      (node (ref "U1") (pin "47") (pinfunction "PB1/TIM1_CH3N/TIM3_CH4/TIM8_CH3N/OTG_HS_INTN/ETH_MII_RXD3/ADC12_IN9_47") (pintype "passive"))
    )
    (net (code "58") (name "/INPUT_27") (class "Default")
      (node (ref "P6") (pin "27") (pinfunction "27_27") (pintype "passive"))
      (node (ref "U1") (pin "49") (pinfunction "PF11/DCMI_D12_49") (pintype "passive"))
    )
    (net (code "59") (name "/INPUT_28") (class "Default")
      (node (ref "P6") (pin "28") (pinfunction "28_28") (pintype "passive"))
      (node (ref "U1") (pin "50") (pinfunction "PF12/FSMC_A6_50") (pintype "passive"))
    )
    (net (code "60") (name "/INPUT_29") (class "Default")
      (node (ref "P6") (pin "29") (pinfunction "29_29") (pintype "passive"))
      (node (ref "U1") (pin "53") (pinfunction "PF13/FSMC_A7_53") (pintype "passive"))
    )
    (net (code "61") (name "/INPUT_30") (class "Default")
      (node (ref "P6") (pin "30") (pinfunction "30_30") (pintype "passive"))
      (node (ref "U1") (pin "54") (pinfunction "PF14/FSMC_A8_54") (pintype "passive"))
    )
    (net (code "62") (name "/INPUT_31") (class "Default")
      (node (ref "P6") (pin "31") (pinfunction "31_31") (pintype "passive"))
      (node (ref "U1") (pin "55") (pinfunction "PF15/FSMC_A9_55") (pintype "passive"))
    )
    (net (code "63") (name "/INPUT_32") (class "Default")
      (node (ref "P6") (pin "32") (pinfunction "32_32") (pintype "passive"))
      (node (ref "U1") (pin "56") (pinfunction "PG0/FSMC_A10_56") (pintype "passive"))
    )
    (net (code "64") (name "/INPUT_33") (class "Default")
      (node (ref "P6") (pin "33") (pinfunction "33_33") (pintype "passive"))
      (node (ref "U1") (pin "57") (pinfunction "PG1/FSMC_A11_57") (pintype "passive"))
    )
    (net (code "65") (name "/INPUT_34") (class "Default")
      (node (ref "P6") (pin "34") (pinfunction "34_34") (pintype "passive"))
      (node (ref "U1") (pin "58") (pinfunction "PE7/FSMC_D4/TIM1_ETR_58") (pintype "passive"))
    )
    (net (code "66") (name "/INPUT_35") (class "Default")
      (node (ref "P6") (pin "35") (pinfunction "35_35") (pintype "passive"))
      (node (ref "U1") (pin "59") (pinfunction "PE8/FSMC_D5/TIM1_CH1N_59") (pintype "passive"))
    )
    (net (code "67") (name "/INPUT_36") (class "Default")
      (node (ref "P6") (pin "36") (pinfunction "36_36") (pintype "passive"))
      (node (ref "U1") (pin "60") (pinfunction "PE9/FSMC_D6/TIM1_CH1_60") (pintype "passive"))
    )
    (net (code "68") (name "/INPUT_37") (class "Default")
      (node (ref "P6") (pin "37") (pinfunction "37_37") (pintype "passive"))
      (node (ref "U1") (pin "63") (pinfunction "PE10/FSMC_D7/TIM1_CH2N_63") (pintype "passive"))
    )
    (net (code "69") (name "/INPUT_38") (class "Default")
      (node (ref "P6") (pin "38") (pinfunction "38_38") (pintype "passive"))
      (node (ref "U1") (pin "64") (pinfunction "PE11/FSMC_D8/TIM1_CH2_64") (pintype "passive"))
    )
    (net (code "70") (name "/INPUT_39") (class "Default")
      (node (ref "P6") (pin "39") (pinfunction "39_39") (pintype "passive"))
      (node (ref "U1") (pin "65") (pinfunction "PE12/FSMC_D9/TIM1_CH3N_65") (pintype "passive"))
    )
    (net (code "71") (name "/INPUT_40") (class "Default")
      (node (ref "P5") (pin "1") (pinfunction "1_1") (pintype "passive"))
      (node (ref "U1") (pin "66") (pinfunction "PE13/FSMC_D10/TIM1_CH3_66") (pintype "passive"))
    )
    (net (code "72") (name "/INPUT_41") (class "Default")
      (node (ref "P5") (pin "2") (pinfunction "2_2") (pintype "passive"))
      (node (ref "U1") (pin "67") (pinfunction "PE14/FSMC_D11/TIM1_CH4_67") (pintype "passive"))
    )
    (net (code "73") (name "/INPUT_42") (class "Default")
      (node (ref "P5") (pin "3") (pinfunction "3_3") (pintype "passive"))
      (node (ref "U1") (pin "68") (pinfunction "PE15/FSMC_D12/TIM1_BKIN_68") (pintype "passive"))
    )
    (net (code "74") (name "/INPUT_43") (class "Default")
      (node (ref "P5") (pin "4") (pinfunction "4_4") (pintype "passive"))
      (node (ref "U1") (pin "69") (pinfunction "PB10/SPI2_SCK/TIM2_CH3/U3_TX/I2C2_SCL/OTG_HS_ULPI_D3/I2S2_CK_69") (pintype "passive"))
    )
    (net (code "75") (name "/INPUT_44") (class "Default")
      (node (ref "P5") (pin "5") (pinfunction "5_5") (pintype "passive"))
      (node (ref "U1") (pin "70") (pinfunction "PB11/TIM2_CH4/U3_RX/I2C2_SDA/HS_ULPI_D4/ETH_MII_TX_EN/ETH_RMII_TX_EN_70") (pintype "passive"))
    )
    (net (code "76") (name "/LED1") (class "Default")
      (node (ref "D1") (pin "K") (pinfunction "K_K") (pintype "passive"))
      (node (ref "U1") (pin "139") (pinfunction "PB8/TIM4_CH3/TIM10_CH1/CAN1_RX/SDIO_D4/ETH_MII_TXD3/I2C1_SCL/DCMI_D6_139") (pintype "passive"))
    )
    (net (code "77") (name "/LED2") (class "Default")
      (node (ref "D2") (pin "K") (pinfunction "K_K") (pintype "passive"))
      (node (ref "U1") (pin "140") (pinfunction "PB9/TIM4_CH4/TIM11_CH1/CAN1_TX/SDIO_D5/SPI2_NSS/I2C1_SDA/DCMI_D7/I2S2_WS_140") (pintype "passive"))
    )
    (net (code "78") (name "/LED3") (class "Default")
      (node (ref "D4") (pin "K") (pinfunction "K_K") (pintype "passive"))
      (node (ref "U1") (pin "141") (pinfunction "PE0/TIM4_ETR/FSMC_NBL0/DCMI_D2_141") (pintype "passive"))
    )
    (net (code "79") (name "/LED4") (class "Default")
      (node (ref "D5") (pin "K") (pinfunction "K_K") (pintype "passive"))
      (node (ref "U1") (pin "142") (pinfunction "PE1/FSMC_NBL1/DCMI_D3_142") (pintype "passive"))
    )
    (net (code "80") (name "/PA0_RS485_TX1") (class "Default")
      (node (ref "U1") (pin "34") (pinfunction "PA0-WKUP/U2_CTS/U4_TX/ETH_MII_CRS/TIM2_CH1_ETR/TIM5_CH1/TIM8_ETR/ADC123_IN0_34") (pintype "passive"))
      (node (ref "U10") (pin "4") (pinfunction "DI_4") (pintype "passive"))
    )
    (net (code "81") (name "/PA1_RS485_RX1") (class "Default")
      (node (ref "U1") (pin "35") (pinfunction "PA1/U2_RTS/U4_RX/ETH_RMII_REF_CLK/ETH_MII_RX_CLK/TIM2_CH2/TIM5_CH2/ADC123_IN1_35") (pintype "passive"))
      (node (ref "U10") (pin "1") (pinfunction "RO_1") (pintype "passive"))
    )
    (net (code "82") (name "/PA2_RS485_RE1") (class "Default")
      (node (ref "U1") (pin "36") (pinfunction "PA2/U2_TX/TIM2_CH3/TIM5_CH3/TIM9_CH1/ETH_MDIO/ADC123_IN2_36") (pintype "passive"))
      (node (ref "U10") (pin "2") (pinfunction "RE_2") (pintype "passive"))
      (node (ref "U10") (pin "3") (pinfunction "DE_3") (pintype "passive"))
    )
    (net (code "83") (name "/PA9_U1_TX") (class "Default")
      (node (ref "U1") (pin "101") (pinfunction "PA9/TIM1_CH2/U1_TX/I2C3_SMBA/OTG_FS_VBUS/DCMI_D0_101") (pintype "passive"))
      (node (ref "U7") (pin "10") (pinfunction "DIN2_10") (pintype "passive"))
    )
    (net (code "84") (name "/PA10_U1_RX") (class "Default")
      (node (ref "U1") (pin "102") (pinfunction "PA10/TIM1_CH3/U1_RX/OTG_FS_ID/DCMI_D1_102") (pintype "passive"))
      (node (ref "U7") (pin "9") (pinfunction "ROUT2_9") (pintype "passive"))
    )
    (net (code "85") (name "/PA13-JTMS") (class "Default")
      (node (ref "P2") (pin "2") (pinfunction "2_2") (pintype "passive"))
      (node (ref "R11") (pin "2") (pinfunction "2_2") (pintype "passive"))
      (node (ref "U1") (pin "105") (pinfunction "PA13/JTMS_SWDIO_105") (pintype "passive"))
    )
    (net (code "86") (name "/PA14-JTCK") (class "Default")
      (node (ref "P2") (pin "1") (pinfunction "1_1") (pintype "passive"))
      (node (ref "R10") (pin "2") (pinfunction "2_2") (pintype "passive"))
      (node (ref "U1") (pin "109") (pinfunction "PA14/JTCK_SWCLK_109") (pintype "passive"))
    )
    (net (code "87") (name "/PC6_U6_TX") (class "Default")
      (node (ref "P1") (pin "1") (pinfunction "1_1") (pintype "passive"))
      (node (ref "U1") (pin "96") (pinfunction "PC6/TIM3_CH1/TIM8_CH1/U6_TX/SDIO_D6/DCMI_D0/I2S2_MCK_96") (pintype "passive"))
    )
    (net (code "88") (name "/PC7_U6_RX") (class "Default")
      (node (ref "P1") (pin "8") (pinfunction "8_8") (pintype "passive"))
      (node (ref "U1") (pin "97") (pinfunction "PC7/TIM3_CH2/TIM8_CH2/U6_RX/SDIO_D7/DCMI_D1/I2S3_MCK_97") (pintype "passive"))
    )
    (net (code "89") (name "/PC8_SDIO_0") (class "Default")
      (node (ref "J1") (pin "7") (pinfunction "DAT0/DO_7") (pintype "passive"))
      (node (ref "R3") (pin "1") (pinfunction "1_1") (pintype "passive"))
      (node (ref "U1") (pin "98") (pinfunction "PC8/TIM3_CH3/TIM8_CH3/U6_CK/SDIO_D0/DCMI_D2_98") (pintype "passive"))
    )
    (net (code "90") (name "/PC9_SDIO_1") (class "Default")
      (node (ref "J1") (pin "8") (pinfunction "DAT1_8") (pintype "passive"))
      (node (ref "R5") (pin "1") (pinfunction "1_1") (pintype "passive"))
      (node (ref "U1") (pin "99") (pinfunction "PC9/TIM3_CH4/TIM8_CH4/I2C3_SDA/SDIO_D1/DCMI_D3/MCO2/I2S_CKIN_99") (pintype "passive"))
    )
    (net (code "91") (name "/PC10_SDIO_2") (class "Default")
      (node (ref "J1") (pin "1") (pinfunction "DAT2_1") (pintype "passive"))
      (node (ref "R6") (pin "1") (pinfunction "1_1") (pintype "passive"))
      (node (ref "U1") (pin "111") (pinfunction "PC10/SPI3_SCK/U3_TX/U4_TX/SDIO_D2/DCMI_D8/I2S3_CK_111") (pintype "passive"))
    )
    (net (code "92") (name "/PC11_SDIO_3") (class "Default")
      (node (ref "J1") (pin "2") (pinfunction "CD/DAT3/CS_2") (pintype "passive"))
      (node (ref "R7") (pin "1") (pinfunction "1_1") (pintype "passive"))
      (node (ref "U1") (pin "112") (pinfunction "PC11/SPI3_MISO/U3_RX/U4_RX/SDIO_D3/DCMI_D4/I2S3ext_SD_112") (pintype "passive"))
    )
    (net (code "93") (name "/PC12_SDIO_CK") (class "Default")
      (node (ref "J1") (pin "5") (pinfunction "CLK/SCLK_5") (pintype "passive"))
      (node (ref "U1") (pin "113") (pinfunction "PC12/SPI3_MOSI/U3_CK/U5_TX/SDIO_CK/DCMI_D9/I2S3_SD_113") (pintype "passive"))
    )
    (net (code "94") (name "/PD2_SDIO_CMD") (class "Default")
      (node (ref "J1") (pin "3") (pinfunction "CMD/DI_3") (pintype "passive"))
      (node (ref "R8") (pin "1") (pinfunction "1_1") (pintype "passive"))
      (node (ref "U1") (pin "116") (pinfunction "PD2/TIM3_ETR/U5_RX/SDIO_CMD/DCMI_D11_116") (pintype "passive"))
    )
    (net (code "95") (name "/PD5_U2_TX") (class "Default")
      (node (ref "U1") (pin "119") (pinfunction "PD5/FSMC_NWE/U2_TX_119") (pintype "passive"))
      (node (ref "U7") (pin "11") (pinfunction "DIN1_11") (pintype "passive"))
    )
    (net (code "96") (name "/PD6_U2_RX") (class "Default")
      (node (ref "U1") (pin "122") (pinfunction "PD6/FSMC_NWAIT/U2_RX_122") (pintype "passive"))
      (node (ref "U7") (pin "12") (pinfunction "ROUT1_12") (pintype "passive"))
    )
    (net (code "97") (name "/POWER_ADC") (class "Default")
      (node (ref "U1") (pin "27") (pinfunction "PC1/ETH_MDC/ADC123_IN11_27") (pintype "passive"))
      (node (ref "U11") (pin "1") (pinfunction "1OUT_1") (pintype "passive"))
      (node (ref "U11") (pin "2") (pinfunction "-_2") (pintype "passive"))
    )
    (net (code "98") (name "/PWM1") (class "Default")
      (node (ref "P8") (pin "4") (pinfunction "4_4") (pintype "passive"))
      (node (ref "U1") (pin "81") (pinfunction "PD12/FSMC_A17/FSMC_ALE/TIM4_CH1/U3_RTS_81") (pintype "passive"))
    )
    (net (code "99") (name "/PWM2") (class "Default")
      (node (ref "P8") (pin "3") (pinfunction "3_3") (pintype "passive"))
      (node (ref "U1") (pin "82") (pinfunction "PD13/FSMC_A18/TIM4_CH2_82") (pintype "passive"))
    )
    (net (code "100") (name "/PWM3") (class "Default")
      (node (ref "P8") (pin "2") (pinfunction "2_2") (pintype "passive"))
      (node (ref "U1") (pin "85") (pinfunction "PD14/FSMC_D0/TIM4_CH3_85") (pintype "passive"))
    )
    (net (code "101") (name "/PWM4") (class "Default")
      (node (ref "P8") (pin "1") (pinfunction "1_1") (pintype "passive"))
      (node (ref "U1") (pin "86") (pinfunction "PD15/FSMC_D1/TIM4_CH4_86") (pintype "passive"))
    )
    (net (code "102") (name "/QYG_KC1") (class "Default")
      (node (ref "P7") (pin "32") (pinfunction "32_32") (pintype "passive"))
      (node (ref "U1") (pin "90") (pinfunction "PG5/FSMC_A15_90") (pintype "passive"))
    )
    (net (code "103") (name "/RESET") (class "Default")
      (node (ref "C1") (pin "1") (pintype "passive"))
      (node (ref "R4") (pin "1") (pintype "passive"))
      (node (ref "RESET1") (pin "1") (pinfunction "1_1") (pintype "passive"))
      (node (ref "U1") (pin "25") (pinfunction "NRST_25") (pintype "passive"))
    )
    (net (code "104") (name "/RS485_1A") (class "Default")
      (node (ref "P7") (pin "7") (pinfunction "7_7") (pintype "passive"))
      (node (ref "R32") (pin "1") (pintype "passive"))
      (node (ref "R33") (pin "1") (pintype "passive"))
      (node (ref "U10") (pin "6") (pinfunction "A_6") (pintype "passive"))
    )
    (net (code "105") (name "/RS485_1B") (class "Default")
      (node (ref "P7") (pin "8") (pinfunction "8_8") (pintype "passive"))
      (node (ref "R33") (pin "2") (pintype "passive"))
      (node (ref "R34") (pin "2") (pintype "passive"))
      (node (ref "U10") (pin "7") (pinfunction "B_7") (pintype "passive"))
    )
    (net (code "106") (name "/SPI2_MISO") (class "Default")
      (node (ref "U1") (pin "75") (pinfunction "PB14/SPI2_MISO/TIM1_CH2N/TIM8_CH2N/TIM12_CH1/U3_RTS/OTG_HS_DM/I2S2ext_SD_75") (pintype "passive"))
      (node (ref "U9") (pin "2") (pinfunction "DO_2") (pintype "passive"))
    )
    (net (code "107") (name "/SPI2_MOSI") (class "Default")
      (node (ref "U1") (pin "76") (pinfunction "PB15/SPI2_MOSI/TIM1_CH3N/TIM8_CH3N/TIM12_CH2/OTG_HS_DP/I2S2_SD_76") (pintype "passive"))
      (node (ref "U9") (pin "5") (pinfunction "DI_5") (pintype "passive"))
    )
    (net (code "108") (name "/SPI2_SCK") (class "Default")
      (node (ref "U1") (pin "74") (pinfunction "PB13/SPI2_SCK/TIM1_CH1N/U3_CTS/CAN2_TX/OTG_HS_ULPI_D6/OTG_HS_VBUS/ETH_MII_TXD1/ETH_RMII_TXD1/I2S2_CK_74") (pintype "passive"))
      (node (ref "U9") (pin "6") (pinfunction "CLK_6") (pintype "passive"))
    )
    (net (code "109") (name "/SSD_KC1") (class "Default")
      (node (ref "P7") (pin "28") (pinfunction "28_28") (pintype "passive"))
      (node (ref "U1") (pin "100") (pinfunction "PA8/TIM1_CH1/U1_CK/I2C3_SCL/MCO1/OTG_FS_SOF_100") (pintype "passive"))
    )
    (net (code "110") (name "/SSD_KC2") (class "Default")
      (node (ref "P7") (pin "27") (pinfunction "27_27") (pintype "passive"))
      (node (ref "U1") (pin "110") (pinfunction "PA15/JTDI/SPI1_NSS/SPI3_NSS/TIM2_CH1_ETR/I2S3_WS_110") (pintype "passive"))
    )
    (net (code "111") (name "/SSD_KC3") (class "Default")
      (node (ref "P7") (pin "26") (pinfunction "26_26") (pintype "passive"))
      (node (ref "U1") (pin "114") (pinfunction "PD0/FSMC_D2/CAN1_RX_114") (pintype "passive"))
    )
    (net (code "112") (name "/TXX_KC1") (class "Default")
      (node (ref "P7") (pin "31") (pinfunction "31_31") (pintype "passive"))
      (node (ref "U1") (pin "91") (pinfunction "PG6/FSMC_INT2_91") (pintype "passive"))
    )
    (net (code "113") (name "/TXX_KC2") (class "Default")
      (node (ref "P7") (pin "30") (pinfunction "30_30") (pintype "passive"))
      (node (ref "U1") (pin "92") (pinfunction "PG7/FSMC_INT3/U6_CK_92") (pintype "passive"))
    )
    (net (code "114") (name "/TXX_KC3") (class "Default")
      (node (ref "P7") (pin "29") (pinfunction "29_29") (pintype "passive"))
      (node (ref "U1") (pin "93") (pinfunction "PG8/U6_RTS/ETH_PPS_OUT_93") (pintype "passive"))
    )
    (net (code "115") (name "/U1_RX") (class "Default")
      (node (ref "P7") (pin "5") (pinfunction "5_5") (pintype "passive"))
      (node (ref "U7") (pin "8") (pinfunction "RIN2_8") (pintype "passive"))
    )
    (net (code "116") (name "/U1_TX") (class "Default")
      (node (ref "P7") (pin "6") (pinfunction "6_6") (pintype "passive"))
      (node (ref "U7") (pin "7") (pinfunction "DOUT2_7") (pintype "passive"))
    )
    (net (code "117") (name "/U2_RX") (class "Default")
      (node (ref "P7") (pin "3") (pinfunction "3_3") (pintype "passive"))
      (node (ref "U7") (pin "13") (pinfunction "RIN1_13") (pintype "passive"))
    )
    (net (code "118") (name "/U2_TX") (class "Default")
      (node (ref "P7") (pin "4") (pinfunction "4_4") (pintype "passive"))
      (node (ref "U7") (pin "14") (pinfunction "DOUT1_14") (pintype "passive"))
    )
    (net (code "119") (name "/U3_RX") (class "Default")
      (node (ref "P3") (pin "4") (pinfunction "4_4") (pintype "passive"))
      (node (ref "U1") (pin "78") (pinfunction "PD9/FSMC_D14/U3_RX_78") (pintype "passive"))
    )
    (net (code "120") (name "/U3_TX") (class "Default")
      (node (ref "P3") (pin "5") (pinfunction "5_5") (pintype "passive"))
      (node (ref "U1") (pin "77") (pinfunction "PD8/FSMC_D13/U3_TX_77") (pintype "passive"))
    )
    (net (code "121") (name "/VBAT") (class "Default")
      (node (ref "C31") (pin "2") (pintype "passive"))
      (node (ref "D6") (pin "2") (pintype "passive"))
      (node (ref "D7") (pin "2") (pintype "passive"))
      (node (ref "U1") (pin "6") (pinfunction "VBAT_6") (pintype "passive"))
    )
    (net (code "122") (name "3.3V") (class "Default")
      (node (ref "C6") (pin "1") (pinfunction "VCC_1") (pintype "passive"))
      (node (ref "C7") (pin "2") (pintype "passive"))
      (node (ref "P1") (pin "5") (pinfunction "5_5") (pintype "passive"))
      (node (ref "P1") (pin "7") (pinfunction "7_7") (pintype "passive"))
      (node (ref "P3") (pin "2") (pinfunction "2_2") (pintype "passive"))
      (node (ref "R13") (pin "1") (pintype "passive"))
      (node (ref "U3") (pin "2") (pinfunction "OUT_2") (pintype "passive"))
      (node (ref "U3") (pin "4") (pinfunction "OUT_4") (pintype "passive"))
    )
    (net (code "123") (name "GND") (class "Default")
      (node (ref "BT1") (pin "2") (pinfunction "-_2") (pintype "passive"))
      (node (ref "C1") (pin "2") (pintype "passive"))
      (node (ref "C10") (pin "1") (pintype "passive"))
      (node (ref "C13") (pin "2") (pintype "passive"))
      (node (ref "C14") (pin "2") (pintype "passive"))
      (node (ref "C19") (pin "1") (pintype "passive"))
      (node (ref "C2") (pin "2") (pintype "passive"))
      (node (ref "C20") (pin "1") (pintype "passive"))
      (node (ref "C21") (pin "1") (pintype "passive"))
      (node (ref "C22") (pin "1") (pintype "passive"))
      (node (ref "C23") (pin "1") (pintype "passive"))
      (node (ref "C24") (pin "1") (pintype "passive"))
      (node (ref "C25") (pin "1") (pintype "passive"))
      (node (ref "C26") (pin "1") (pintype "passive"))
      (node (ref "C27") (pin "1") (pintype "passive"))
      (node (ref "C28") (pin "1") (pintype "passive"))
      (node (ref "C29") (pin "1") (pintype "passive"))
      (node (ref "C3") (pin "1") (pintype "passive"))
      (node (ref "C30") (pin "1") (pintype "passive"))
      (node (ref "C31") (pin "1") (pintype "passive"))
      (node (ref "C36") (pin "1") (pintype "passive"))
      (node (ref "C38") (pin "2") (pinfunction "GND_2") (pintype "passive"))
      (node (ref "C4") (pin "1") (pintype "passive"))
      (node (ref "C40") (pin "1") (pintype "passive"))
      (node (ref "C42") (pin "2") (pinfunction "2_2") (pintype "passive"))
      (node (ref "C43") (pin "2") (pintype "passive"))
      (node (ref "C44") (pin "2") (pintype "passive"))
      (node (ref "C5") (pin "1") (pintype "passive"))
      (node (ref "C6") (pin "2") (pinfunction "GND_2") (pintype "passive"))
      (node (ref "C7") (pin "1") (pintype "passive"))
      (node (ref "D8") (pin "K") (pinfunction "K_K") (pintype "passive"))
      (node (ref "H1") (pin "5") (pinfunction "5_5") (pintype "passive"))
      (node (ref "H1") (pin "6") (pinfunction "6_6") (pintype "passive"))
      (node (ref "J1") (pin "6") (pinfunction "VSS_6") (pintype "passive"))
      (node (ref "J1") (pin "9") (pinfunction "Cd_9") (pintype "passive"))
      (node (ref "J3") (pin "1") (pinfunction "-VIN_1") (pintype "passive"))
      (node (ref "J3") (pin "5") (pinfunction "GND_5") (pintype "passive"))
      (node (ref "P1") (pin "4") (pinfunction "4_4") (pintype "passive"))
      (node (ref "P2") (pin "3") (pinfunction "3_3") (pintype "passive"))
      (node (ref "P3") (pin "1") (pinfunction "1_1") (pintype "passive"))
      (node (ref "P3") (pin "6") (pinfunction "6_6") (pintype "passive"))
      (node (ref "P3") (pin "7") (pinfunction "7_7") (pintype "passive"))
      (node (ref "P6") (pin "40") (pinfunction "40_40") (pintype "passive"))
      (node (ref "P7") (pin "2") (pinfunction "2_2") (pintype "passive"))
      (node (ref "Q4") (pin "1") (pinfunction "E_1") (pintype "passive"))
      (node (ref "R10") (pin "1") (pinfunction "1_1") (pintype "passive"))
      (node (ref "R34") (pin "1") (pintype "passive"))
      (node (ref "R36") (pin "1") (pinfunction "1_1") (pintype "passive"))
      (node (ref "R41") (pin "1") (pintype "passive"))
      (node (ref "RESET1") (pin "2") (pinfunction "2_2") (pintype "passive"))
      (node (ref "U1") (pin "107") (pinfunction "VSS_107") (pintype "passive"))
      (node (ref "U1") (pin "120") (pinfunction "VSS_120") (pintype "passive"))
      (node (ref "U1") (pin "130") (pinfunction "VSS_130") (pintype "passive"))
      (node (ref "U1") (pin "16") (pinfunction "VSS_16") (pintype "passive"))
      (node (ref "U1") (pin "31") (pinfunction "VSSA_31") (pintype "passive"))
      (node (ref "U1") (pin "38") (pinfunction "VSS_38") (pintype "passive"))
      (node (ref "U1") (pin "51") (pinfunction "VSS_51") (pintype "passive"))
      (node (ref "U1") (pin "61") (pinfunction "VSS_61") (pintype "passive"))
      (node (ref "U1") (pin "83") (pinfunction "VSS_83") (pintype "passive"))
      (node (ref "U1") (pin "94") (pinfunction "VSS_94") (pintype "passive"))
      (node (ref "U10") (pin "5") (pinfunction "GND_5") (pintype "passive"))
      (node (ref "U11") (pin "11") (pinfunction "GND_11") (pintype "passive"))
      (node (ref "U2") (pin "2") (pinfunction "GND_2") (pintype "power_in"))
      (node (ref "U2") (pin "8") (pinfunction "RS_8") (pintype "input"))
      (node (ref "U3") (pin "1") (pinfunction "GND_1") (pintype "passive"))
      (node (ref "U7") (pin "15") (pinfunction "GND_15") (pintype "passive"))
      (node (ref "U8") (pin "1") (pinfunction "GND_1") (pintype "passive"))
      (node (ref "U9") (pin "4") (pinfunction "GND_4") (pintype "passive"))
    )
    (net (code "124") (name "Net-(BEEP1-G)") (class "Default")
      (node (ref "BEEP1") (pin "2") (pinfunction "G_2") (pintype "passive"))
      (node (ref "Q4") (pin "3") (pinfunction "C_3") (pintype "passive"))
    )
    (net (code "125") (name "Net-(BT1-+)") (class "Default")
      (node (ref "BT1") (pin "1") (pinfunction "+_1") (pintype "passive"))
      (node (ref "D7") (pin "1") (pintype "passive"))
    )
    (net (code "126") (name "Net-(D1-PadA)") (class "Default")
      (node (ref "D1") (pin "A") (pinfunction "A_A") (pintype "passive"))
      (node (ref "PR1") (pin "1") (pinfunction "1_1") (pintype "passive"))
    )
    (net (code "127") (name "Net-(D2-PadA)") (class "Default")
      (node (ref "D2") (pin "A") (pinfunction "A_A") (pintype "passive"))
      (node (ref "PR1") (pin "2") (pinfunction "2_2") (pintype "passive"))
    )
    (net (code "128") (name "Net-(D3-PadA)") (class "Default")
      (node (ref "D3") (pin "A") (pinfunction "A_A") (pintype "passive"))
      (node (ref "R13") (pin "2") (pintype "passive"))
    )
    (net (code "129") (name "Net-(D4-PadA)") (class "Default")
      (node (ref "D4") (pin "A") (pinfunction "A_A") (pintype "passive"))
      (node (ref "PR1") (pin "3") (pinfunction "3_3") (pintype "passive"))
    )
    (net (code "130") (name "Net-(D5-PadA)") (class "Default")
      (node (ref "D5") (pin "A") (pinfunction "A_A") (pintype "passive"))
      (node (ref "PR1") (pin "4") (pinfunction "4_4") (pintype "passive"))
    )
    (net (code "131") (name "Net-(D8-PadA)") (class "Default")
      (node (ref "D8") (pin "A") (pinfunction "A_A") (pintype "passive"))
      (node (ref "R25") (pin "2") (pintype "passive"))
    )
    (net (code "132") (name "Net-(H1-Pad3)") (class "Default")
      (node (ref "H1") (pin "3") (pinfunction "3_3") (pintype "passive"))
      (node (ref "R1") (pin "2") (pintype "passive"))
    )
    (net (code "133") (name "Net-(H1-Pad4)") (class "Default")
      (node (ref "H1") (pin "4") (pinfunction "4_4") (pintype "passive"))
      (node (ref "R2") (pin "1") (pintype "passive"))
    )
    (net (code "134") (name "Net-(K1-TAP1)") (class "Default")
      (node (ref "K1") (pin "2") (pinfunction "TAP1_2") (pintype "passive"))
      (node (ref "U3") (pin "3") (pinfunction "IN_3") (pintype "passive"))
      (node (ref "U8") (pin "3") (pinfunction "IN_3") (pintype "passive"))
    )
    (net (code "135") (name "Net-(Q4-B)") (class "Default")
      (node (ref "Q4") (pin "2") (pinfunction "B_2") (pintype "passive"))
      (node (ref "R40") (pin "2") (pintype "passive"))
      (node (ref "R41") (pin "2") (pintype "passive"))
    )
    (net (code "136") (name "Net-(U1-PC14-OSC32_IN)") (class "Default")
      (node (ref "C3") (pin "2") (pintype "passive"))
      (node (ref "U1") (pin "8") (pinfunction "PC14-OSC32_IN_8") (pintype "passive"))
      (node (ref "Y1") (pin "2") (pinfunction "OSC2_2") (pintype "passive"))
    )
    (net (code "137") (name "Net-(U1-PC15-OSC32_OUT)") (class "Default")
      (node (ref "C5") (pin "2") (pintype "passive"))
      (node (ref "U1") (pin "9") (pinfunction "PC15-OSC32_OUT_9") (pintype "passive"))
      (node (ref "Y1") (pin "1") (pinfunction "OSC1_1") (pintype "passive"))
    )
    (net (code "138") (name "Net-(U1-PDR_ON)") (class "Default")
      (node (ref "R20") (pin "1") (pintype "passive"))
      (node (ref "U1") (pin "143") (pinfunction "PDR_ON_143") (pintype "passive"))
    )
    (net (code "139") (name "Net-(U1-PH0-OSC_IN)") (class "Default")
      (node (ref "C4") (pin "2") (pintype "passive"))
      (node (ref "R12") (pin "2") (pintype "passive"))
      (node (ref "U1") (pin "23") (pinfunction "PH0-OSC_IN_23") (pintype "passive"))
      (node (ref "Y2") (pin "2") (pinfunction "OSC2_2") (pintype "passive"))
    )
    (net (code "140") (name "Net-(U1-PH1-OSC_OUT)") (class "Default")
      (node (ref "C10") (pin "2") (pintype "passive"))
      (node (ref "R12") (pin "1") (pintype "passive"))
      (node (ref "U1") (pin "24") (pinfunction "PH1-OSC_OUT_24") (pintype "passive"))
      (node (ref "Y2") (pin "1") (pinfunction "OSC1_1") (pintype "passive"))
    )
    (net (code "141") (name "Net-(U1-Vcap_1)") (class "Default")
      (node (ref "C13") (pin "1") (pintype "passive"))
      (node (ref "U1") (pin "71") (pinfunction "Vcap_1_71") (pintype "passive"))
    )
    (net (code "142") (name "Net-(U1-Vcap_2)") (class "Default")
      (node (ref "C14") (pin "1") (pintype "passive"))
      (node (ref "U1") (pin "106") (pinfunction "Vcap_2_106") (pintype "passive"))
    )
    (net (code "143") (name "Net-(U7-C1+)") (class "Default")
      (node (ref "C37") (pin "1") (pinfunction "1_1") (pintype "passive"))
      (node (ref "U7") (pin "1") (pinfunction "C1+_1") (pintype "passive"))
    )
    (net (code "144") (name "Net-(U7-C1-)") (class "Default")
      (node (ref "C37") (pin "2") (pinfunction "2_2") (pintype "passive"))
      (node (ref "U7") (pin "3") (pinfunction "C1-_3") (pintype "passive"))
    )
    (net (code "145") (name "Net-(U7-C2+)") (class "Default")
      (node (ref "C41") (pin "1") (pinfunction "1_1") (pintype "passive"))
      (node (ref "U7") (pin "4") (pinfunction "C2+_4") (pintype "passive"))
    )
    (net (code "146") (name "Net-(U7-C2-)") (class "Default")
      (node (ref "C41") (pin "2") (pinfunction "2_2") (pintype "passive"))
      (node (ref "U7") (pin "5") (pinfunction "C2-_5") (pintype "passive"))
    )
    (net (code "147") (name "Net-(U7-V+)") (class "Default")
      (node (ref "C39") (pin "1") (pinfunction "1_1") (pintype "passive"))
      (node (ref "U7") (pin "2") (pinfunction "V+_2") (pintype "passive"))
    )
    (net (code "148") (name "Net-(U7-V-)") (class "Default")
      (node (ref "C42") (pin "1") (pinfunction "1_1") (pintype "passive"))
      (node (ref "U7") (pin "6") (pinfunction "V-_6") (pintype "passive"))
    )
    (net (code "149") (name "Net-(U11A-+)") (class "Default")
      (node (ref "R35") (pin "1") (pinfunction "1_1") (pintype "passive"))
      (node (ref "R36") (pin "2") (pinfunction "2_2") (pintype "passive"))
      (node (ref "U11") (pin "3") (pinfunction "+_3") (pintype "passive"))
    )
    (net (code "150") (name "VCC") (class "Default")
      (node (ref "C2") (pin "1") (pintype "passive"))
      (node (ref "J3") (pin "3") (pinfunction "+V0_3") (pintype "passive"))
      (node (ref "K1") (pin "3") (pinfunction "I/O1_3") (pintype "passive"))
      (node (ref "P8") (pin "6") (pinfunction "6_6") (pintype "passive"))
      (node (ref "U11") (pin "4") (pinfunction "VCC_4") (pintype "passive"))
      (node (ref "U2") (pin "3") (pinfunction "VCC_3") (pintype "power_in"))
    )
    (net (code "151") (name "VCC3.3") (class "Default")
      (node (ref "BEEP1") (pin "1") (pinfunction "P_1") (pintype "passive"))
      (node (ref "C19") (pin "2") (pintype "passive"))
      (node (ref "C20") (pin "2") (pintype "passive"))
      (node (ref "C21") (pin "2") (pintype "passive"))
      (node (ref "C22") (pin "2") (pintype "passive"))
      (node (ref "C23") (pin "2") (pintype "passive"))
      (node (ref "C24") (pin "2") (pintype "passive"))
      (node (ref "C25") (pin "2") (pintype "passive"))
      (node (ref "C26") (pin "2") (pintype "passive"))
      (node (ref "C27") (pin "2") (pintype "passive"))
      (node (ref "C28") (pin "2") (pintype "passive"))
      (node (ref "C29") (pin "2") (pintype "passive"))
      (node (ref "C30") (pin "2") (pintype "passive"))
      (node (ref "C36") (pin "2") (pintype "passive"))
      (node (ref "C38") (pin "1") (pinfunction "VCC_1") (pintype "passive"))
      (node (ref "C39") (pin "2") (pinfunction "2_2") (pintype "passive"))
      (node (ref "C40") (pin "2") (pintype "passive"))
      (node (ref "C43") (pin "1") (pintype "passive"))
      (node (ref "C44") (pin "1") (pintype "passive"))
      (node (ref "D6") (pin "1") (pintype "passive"))
      (node (ref "H1") (pin "1") (pinfunction "1_1") (pintype "passive"))
      (node (ref "H1") (pin "2") (pinfunction "2_2") (pintype "passive"))
      (node (ref "J1") (pin "4") (pinfunction "VDD_4") (pintype "passive"))
      (node (ref "P2") (pin "4") (pinfunction "4_4") (pintype "passive"))
      (node (ref "P7") (pin "36") (pinfunction "36_36") (pintype "passive"))
      (node (ref "P8") (pin "5") (pinfunction "5_5") (pintype "passive"))
      (node (ref "PR1") (pin "5") (pinfunction "5_5") (pintype "passive"))
      (node (ref "PR1") (pin "6") (pinfunction "6_6") (pintype "passive"))
      (node (ref "PR1") (pin "7") (pinfunction "7_7") (pintype "passive"))
      (node (ref "PR1") (pin "8") (pinfunction "8_8") (pintype "passive"))
      (node (ref "R11") (pin "1") (pinfunction "1_1") (pintype "passive"))
      (node (ref "R20") (pin "2") (pintype "passive"))
      (node (ref "R25") (pin "1") (pintype "passive"))
      (node (ref "R3") (pin "2") (pinfunction "2_2") (pintype "passive"))
      (node (ref "R32") (pin "2") (pintype "passive"))
      (node (ref "R4") (pin "2") (pintype "passive"))
      (node (ref "R5") (pin "2") (pinfunction "2_2") (pintype "passive"))
      (node (ref "R6") (pin "2") (pinfunction "2_2") (pintype "passive"))
      (node (ref "R7") (pin "2") (pinfunction "2_2") (pintype "passive"))
      (node (ref "R8") (pin "2") (pinfunction "2_2") (pintype "passive"))
      (node (ref "U1") (pin "108") (pinfunction "VDD_108") (pintype "passive"))
      (node (ref "U1") (pin "121") (pinfunction "VDD_121") (pintype "passive"))
      (node (ref "U1") (pin "131") (pinfunction "VDD_131") (pintype "passive"))
      (node (ref "U1") (pin "144") (pinfunction "VDD_144") (pintype "passive"))
      (node (ref "U1") (pin "17") (pinfunction "VDD_17") (pintype "passive"))
      (node (ref "U1") (pin "30") (pinfunction "VDD_30") (pintype "passive"))
      (node (ref "U1") (pin "32") (pinfunction "Vref+_32") (pintype "passive"))
      (node (ref "U1") (pin "33") (pinfunction "VDDA_33") (pintype "passive"))
      (node (ref "U1") (pin "39") (pinfunction "VDD_39") (pintype "passive"))
      (node (ref "U1") (pin "52") (pinfunction "VDD_52") (pintype "passive"))
      (node (ref "U1") (pin "62") (pinfunction "VDD_62") (pintype "passive"))
      (node (ref "U1") (pin "72") (pinfunction "VDD_72") (pintype "passive"))
      (node (ref "U1") (pin "84") (pinfunction "VDD_84") (pintype "passive"))
      (node (ref "U1") (pin "95") (pinfunction "VDD_95") (pintype "passive"))
      (node (ref "U10") (pin "8") (pinfunction "VCC_8") (pintype "passive"))
      (node (ref "U7") (pin "16") (pinfunction "VCC_16") (pintype "passive"))
      (node (ref "U8") (pin "2") (pinfunction "OUT_2") (pintype "passive"))
      (node (ref "U8") (pin "4") (pinfunction "OUT_4") (pintype "passive"))
      (node (ref "U9") (pin "3") (pinfunction "~{WP}_3") (pintype "passive"))
      (node (ref "U9") (pin "7") (pinfunction "~{HOLD}_7") (pintype "passive"))
      (node (ref "U9") (pin "8") (pinfunction "VCC_8") (pintype "passive"))
    )
    (net (code "152") (name "VCC24") (class "Default")
      (node (ref "J3") (pin "2") (pinfunction "+VIN_2") (pintype "passive"))
      (node (ref "P7") (pin "1") (pinfunction "1_1") (pintype "passive"))
      (node (ref "R35") (pin "2") (pinfunction "2_2") (pintype "passive"))
    )
    (net (code "153") (name "unconnected-(J1-GROUND-Pad10)") (class "Default")
      (node (ref "J1") (pin "10") (pinfunction "GROUND_10") (pintype "passive"))
    )
    (net (code "154") (name "unconnected-(J1-GROUND-Pad11)") (class "Default")
      (node (ref "J1") (pin "11") (pinfunction "GROUND_11") (pintype "passive"))
    )
    (net (code "155") (name "unconnected-(J1-GROUND-Pad12)") (class "Default")
      (node (ref "J1") (pin "12") (pinfunction "GROUND_12") (pintype "passive"))
    )
    (net (code "156") (name "unconnected-(J1-GROUND-Pad13)") (class "Default")
      (node (ref "J1") (pin "13") (pinfunction "GROUND_13") (pintype "passive"))
    )
    (net (code "157") (name "unconnected-(J3-NC-Pad4)") (class "Default")
      (node (ref "J3") (pin "4") (pinfunction "NC_4") (pintype "passive"))
    )
    (net (code "158") (name "unconnected-(K1-I{slash}O1-Pad1)") (class "Default")
      (node (ref "K1") (pin "1") (pinfunction "I/O1_1") (pintype "passive"))
    )
    (net (code "159") (name "unconnected-(K1-I{slash}O2-Pad4)") (class "Default")
      (node (ref "K1") (pin "4") (pinfunction "I/O2_4") (pintype "passive"))
    )
    (net (code "160") (name "unconnected-(K1-I{slash}O2-Pad6)") (class "Default")
      (node (ref "K1") (pin "6") (pinfunction "I/O2_6") (pintype "passive"))
    )
    (net (code "161") (name "unconnected-(K1-TAP2-Pad5)") (class "Default")
      (node (ref "K1") (pin "5") (pinfunction "TAP2_5") (pintype "passive"))
    )
    (net (code "162") (name "unconnected-(P1-Pad2)") (class "Default")
      (node (ref "P1") (pin "2") (pinfunction "2_2") (pintype "passive"))
    )
    (net (code "163") (name "unconnected-(P1-Pad3)") (class "Default")
      (node (ref "P1") (pin "3") (pinfunction "3_3") (pintype "passive"))
    )
    (net (code "164") (name "unconnected-(P1-Pad6)") (class "Default")
      (node (ref "P1") (pin "6") (pinfunction "6_6") (pintype "passive"))
    )
    (net (code "165") (name "unconnected-(P5-Pad6)") (class "Default")
      (node (ref "P5") (pin "6") (pinfunction "6_6") (pintype "passive"))
    )
    (net (code "166") (name "unconnected-(U1-PD7{slash}FSMC_NE1{slash}FSMC_NCE2{slash}U2_CK-Pad123)") (class "Default")
      (node (ref "U1") (pin "123") (pinfunction "PD7/FSMC_NE1/FSMC_NCE2/U2_CK_123") (pintype "passive"))
    )
    (net (code "167") (name "unconnected-(U1-PD10{slash}FSMC_D15{slash}U3_CK-Pad79)") (class "Default")
      (node (ref "U1") (pin "79") (pinfunction "PD10/FSMC_D15/U3_CK_79") (pintype "passive"))
    )
    (net (code "168") (name "unconnected-(U1-PD11{slash}FSMC_A16{slash}FSMC_CLE{slash}U3_CTS-Pad80)") (class "Default")
      (node (ref "U1") (pin "80") (pinfunction "PD11/FSMC_A16/FSMC_CLE/U3_CTS_80") (pintype "passive"))
    )
    (net (code "169") (name "unconnected-(U2-Vref-Pad5)") (class "Default")
      (node (ref "U2") (pin "5") (pinfunction "Vref_5") (pintype "output"))
    )
  )
)
